# PT_2016_PB_MAIN_Rev1.net
KiCad netlist of a schematic drawn in EAGLE
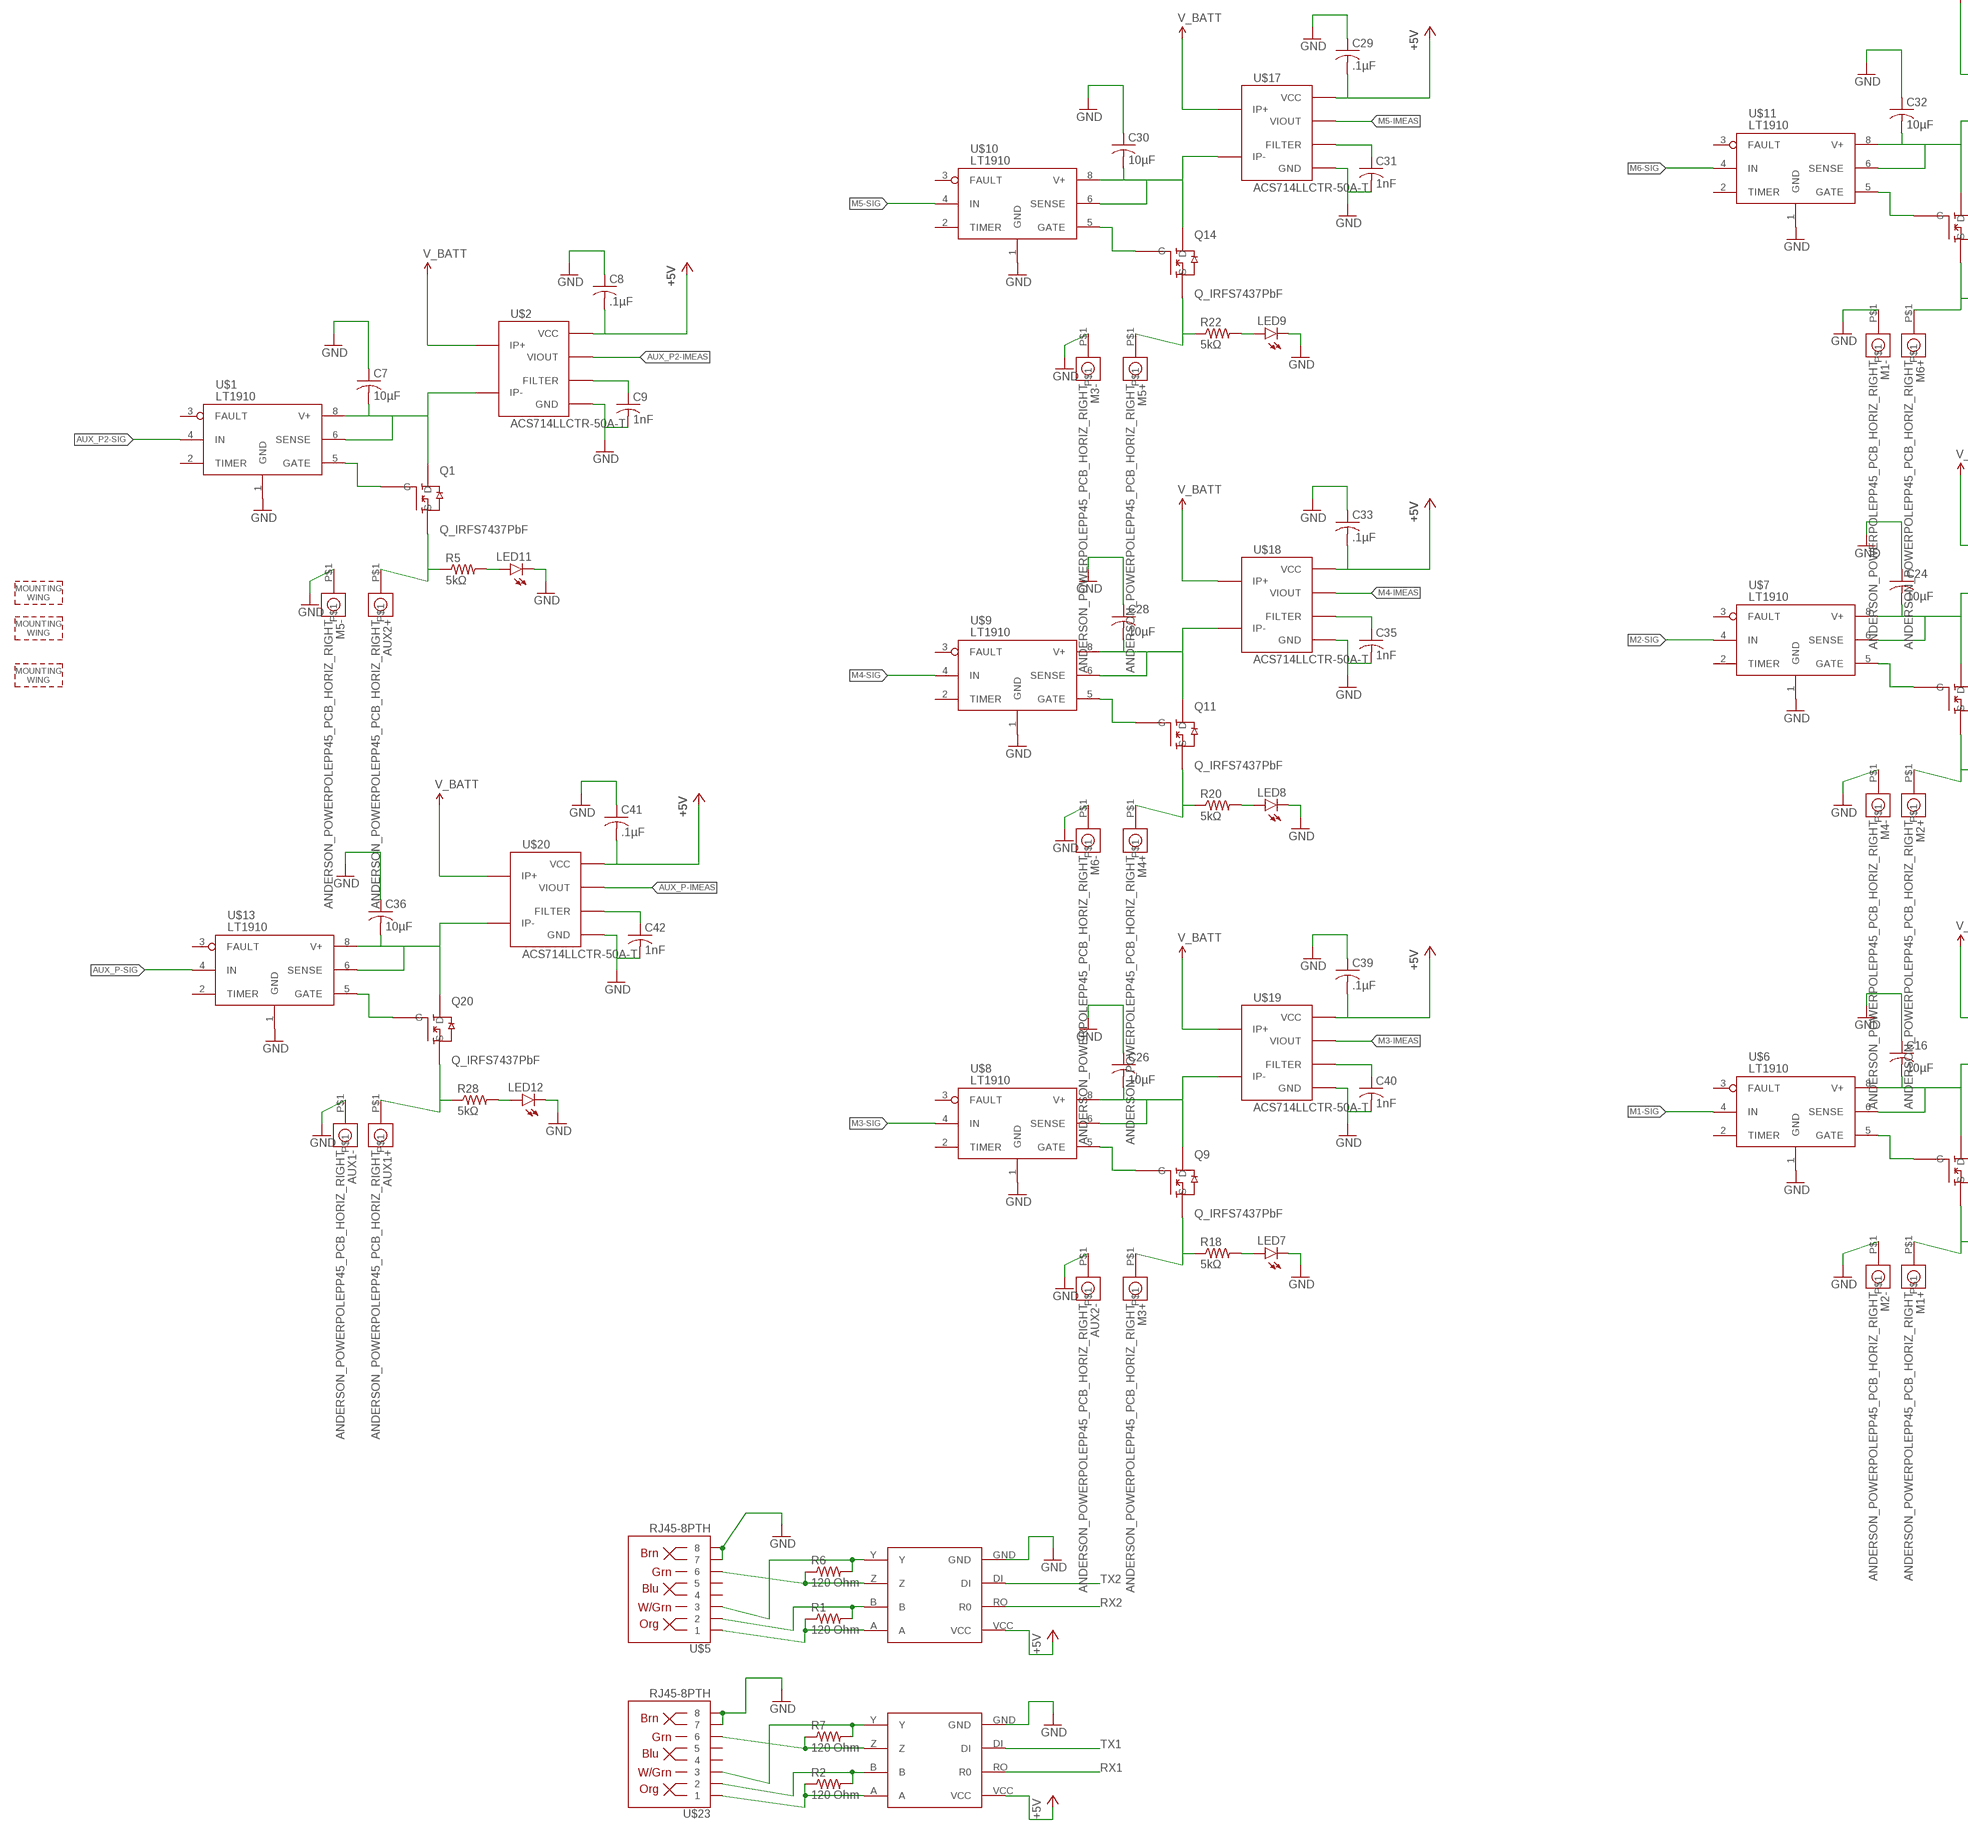
[diagram p0: schematic, sheet 1, part 1 of 3]
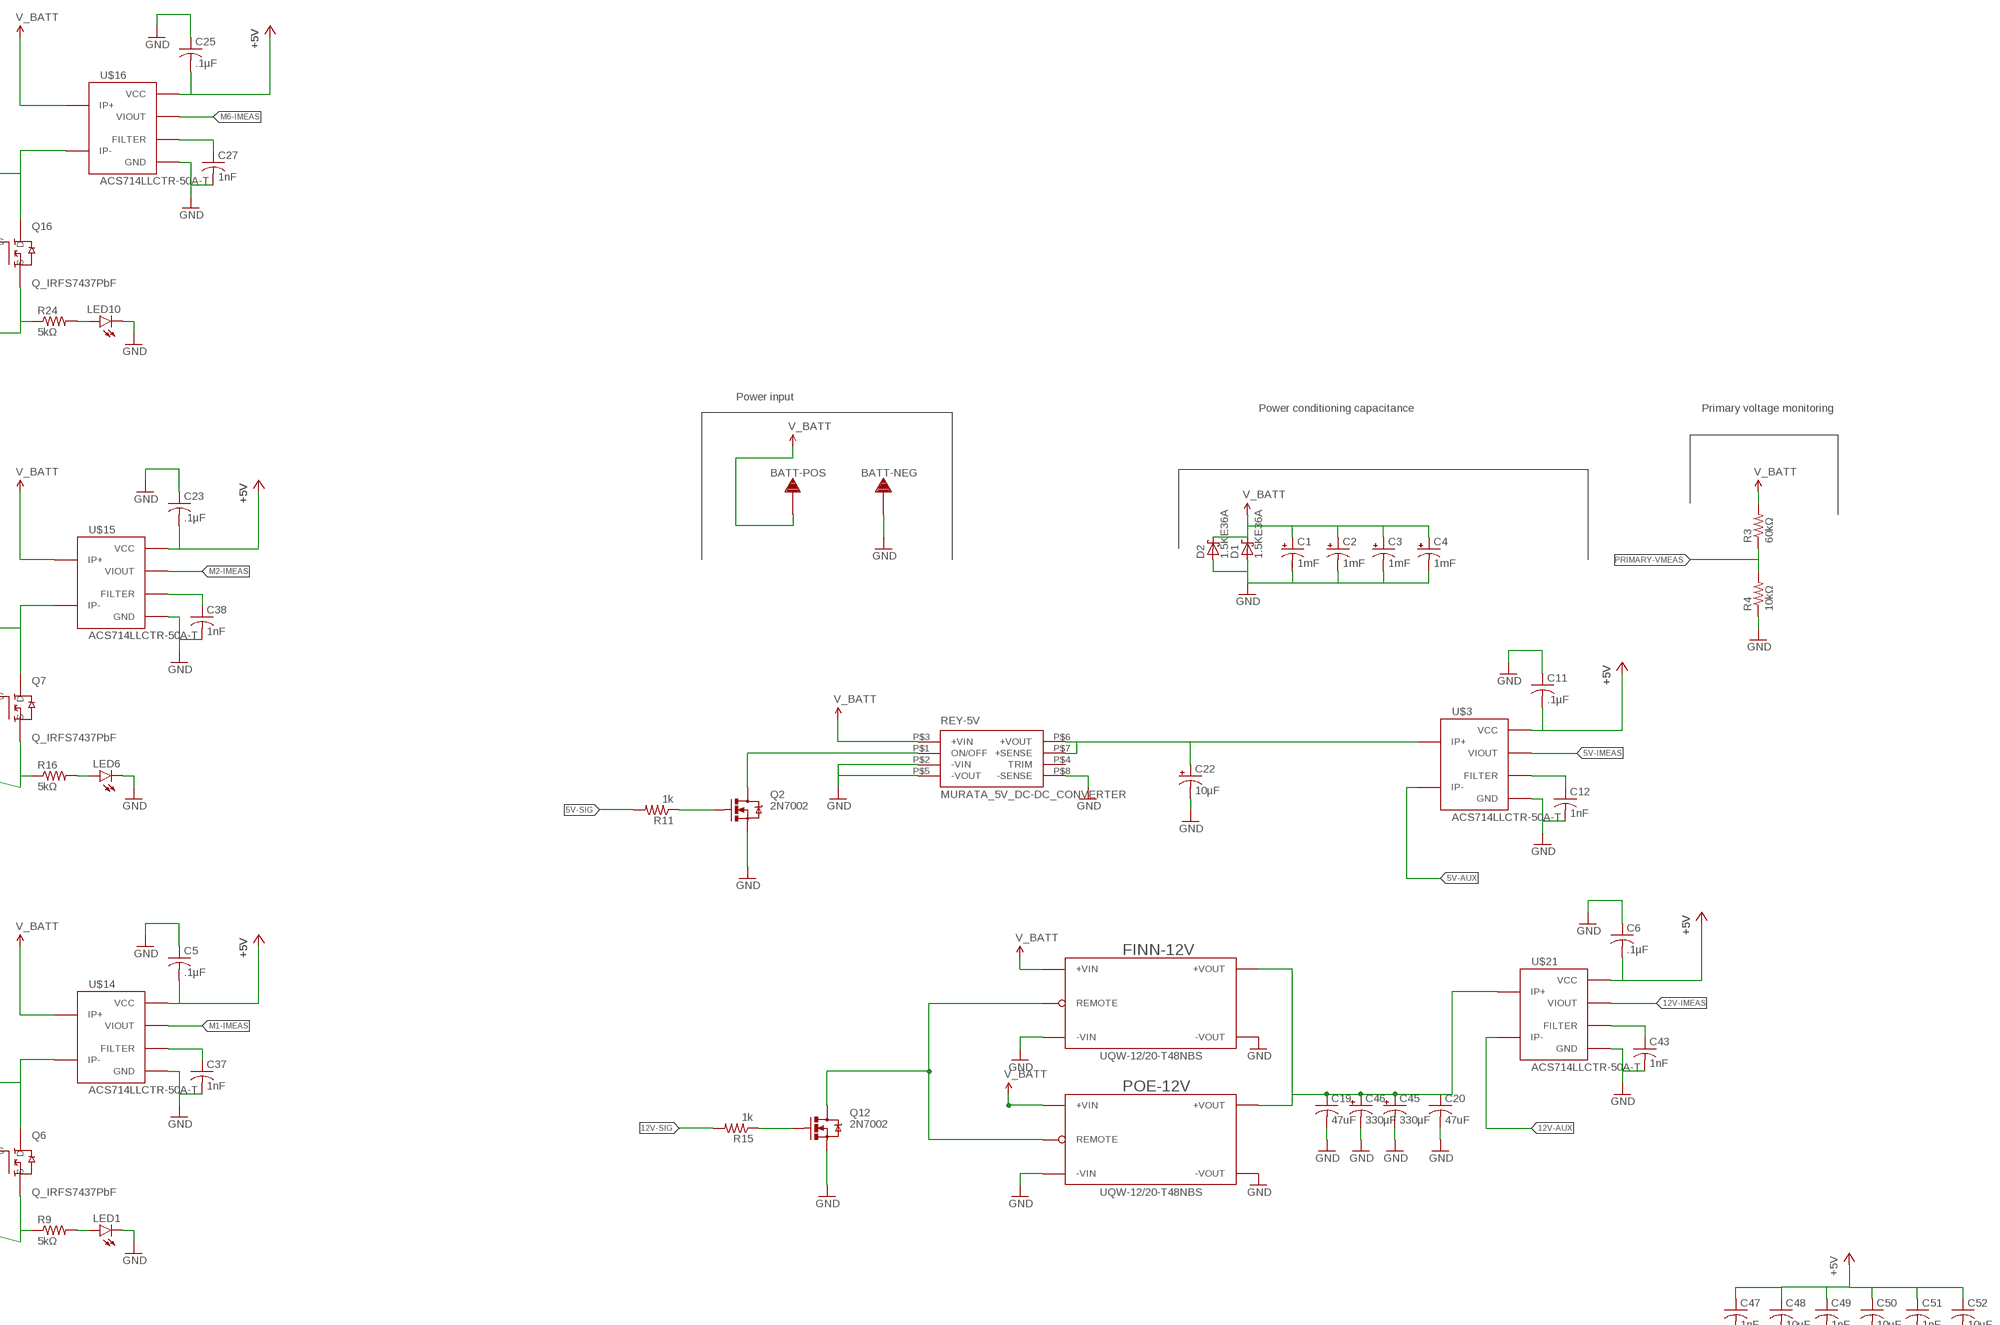
[diagram p1: schematic, sheet 1, part 2 of 3]
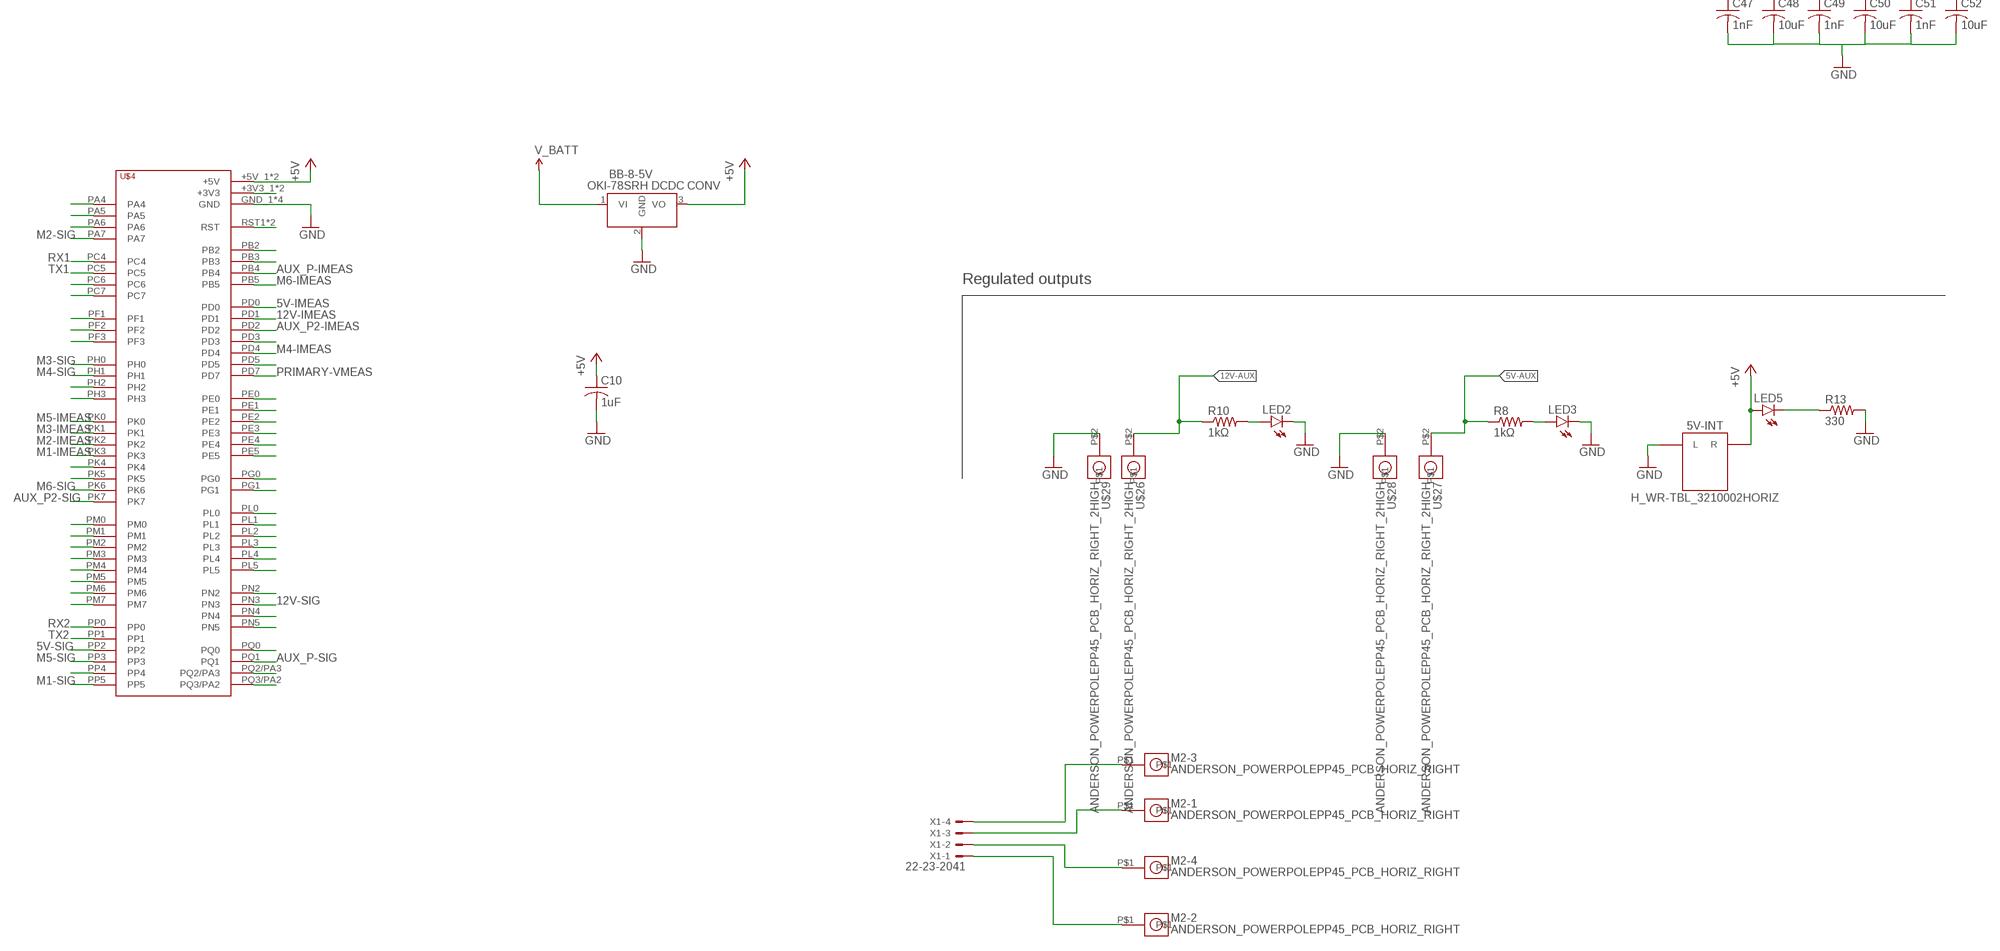
[diagram p2: schematic, sheet 1, part 3 of 3]

(export (version "E")
  (design (tool "Eeschema 10.0.6"))
  (components
    (comp (ref "5V-INT")
      (value "H_WR-TBL_3210002HORIZ")
      (footprint "eagle-import:691322110002")
      (libsource (lib "eagle-import") (part "H_WR-TBL_3210002HORIZ"))
    )
    (comp (ref "AUX1+")
      (value "ANDERSON_POWERPOLEPP45_PCB_HORIZ_RIGHT")
      (footprint "eagle-import:APP45_PCB_HORIZ_RIGHT")
      (libsource (lib "eagle-import") (part "ANDERSON_POWERPOLEPP45_PCB_HORIZ_RIGHT"))
    )
    (comp (ref "AUX1-")
      (value "ANDERSON_POWERPOLEPP45_PCB_HORIZ_RIGHT")
      (footprint "eagle-import:APP45_PCB_HORIZ_RIGHT")
      (libsource (lib "eagle-import") (part "ANDERSON_POWERPOLEPP45_PCB_HORIZ_RIGHT"))
    )
    (comp (ref "AUX2+")
      (value "ANDERSON_POWERPOLEPP45_PCB_HORIZ_RIGHT")
      (footprint "eagle-import:APP45_PCB_HORIZ_RIGHT")
      (libsource (lib "eagle-import") (part "ANDERSON_POWERPOLEPP45_PCB_HORIZ_RIGHT"))
    )
    (comp (ref "AUX2-")
      (value "ANDERSON_POWERPOLEPP45_PCB_HORIZ_RIGHT")
      (footprint "eagle-import:APP45_PCB_HORIZ_RIGHT")
      (libsource (lib "eagle-import") (part "ANDERSON_POWERPOLEPP45_PCB_HORIZ_RIGHT"))
    )
    (comp (ref "BATT-NEG")
      (value "TERMINAL_HOLE")
      (footprint "eagle-import:LARGE_TERMINAL_HOLE")
      (libsource (lib "eagle-import") (part "TERMINAL_HOLE"))
    )
    (comp (ref "BATT-POS")
      (value "TERMINAL_HOLE")
      (footprint "eagle-import:LARGE_TERMINAL_HOLE")
      (libsource (lib "eagle-import") (part "TERMINAL_HOLE"))
    )
    (comp (ref "BB-8-5V")
      (value "Q_OKI-78SR")
      (footprint "eagle-import:OKI-78SRH")
      (libsource (lib "eagle-import") (part "Q_OKI-78SR"))
    )
    (comp (ref "C1")
      (value "1mF")
      (footprint "eagle-import:C_12.5MM")
      (libsource (lib "eagle-import") (part "C_POL12.5MM_NORMAL"))
    )
    (comp (ref "C2")
      (value "1mF")
      (footprint "eagle-import:C_12.5MM")
      (libsource (lib "eagle-import") (part "C_POL12.5MM_NORMAL"))
    )
    (comp (ref "C3")
      (value "1mF")
      (footprint "eagle-import:C_12.5MM")
      (libsource (lib "eagle-import") (part "C_POL12.5MM_NORMAL"))
    )
    (comp (ref "C4")
      (value "1mF")
      (footprint "eagle-import:C_12.5MM")
      (libsource (lib "eagle-import") (part "C_POL12.5MM_NORMAL"))
    )
    (comp (ref "C5")
      (value ".1µF")
      (footprint "eagle-import:C1206")
      (libsource (lib "eagle-import") (part "C-USC1206"))
    )
    (comp (ref "C6")
      (value ".1µF")
      (footprint "eagle-import:C1206")
      (libsource (lib "eagle-import") (part "C-USC1206"))
    )
    (comp (ref "C7")
      (value "10µF")
      (footprint "eagle-import:C1206")
      (libsource (lib "eagle-import") (part "C-USC1206"))
    )
    (comp (ref "C8")
      (value ".1µF")
      (footprint "eagle-import:C1206")
      (libsource (lib "eagle-import") (part "C-USC1206"))
    )
    (comp (ref "C9")
      (value "1nF")
      (footprint "eagle-import:C1206")
      (libsource (lib "eagle-import") (part "C-USC1206"))
    )
    (comp (ref "C10")
      (value "1uF")
      (footprint "eagle-import:C1206")
      (libsource (lib "eagle-import") (part "C-USC1206"))
    )
    (comp (ref "C11")
      (value ".1µF")
      (footprint "eagle-import:C1206")
      (libsource (lib "eagle-import") (part "C-USC1206"))
    )
    (comp (ref "C12")
      (value "1nF")
      (footprint "eagle-import:C1206")
      (libsource (lib "eagle-import") (part "C-USC1206"))
    )
    (comp (ref "C16")
      (value "10µF")
      (footprint "eagle-import:C1206")
      (libsource (lib "eagle-import") (part "C-USC1206"))
    )
    (comp (ref "C19")
      (value "47uF")
      (footprint "eagle-import:C1206")
      (libsource (lib "eagle-import") (part "C-USC1206"))
    )
    (comp (ref "C20")
      (value "47uF")
      (footprint "eagle-import:C1206")
      (libsource (lib "eagle-import") (part "C-USC1206"))
    )
    (comp (ref "C22")
      (value "10µF")
      (footprint "eagle-import:E5-8,5")
      (libsource (lib "eagle-import") (part "CPOL-USE5-8.5"))
    )
    (comp (ref "C23")
      (value ".1µF")
      (footprint "eagle-import:C1206")
      (libsource (lib "eagle-import") (part "C-USC1206"))
    )
    (comp (ref "C24")
      (value "10µF")
      (footprint "eagle-import:C1206")
      (libsource (lib "eagle-import") (part "C-USC1206"))
    )
    (comp (ref "C25")
      (value ".1µF")
      (footprint "eagle-import:C1206")
      (libsource (lib "eagle-import") (part "C-USC1206"))
    )
    (comp (ref "C26")
      (value "10µF")
      (footprint "eagle-import:C1206")
      (libsource (lib "eagle-import") (part "C-USC1206"))
    )
    (comp (ref "C27")
      (value "1nF")
      (footprint "eagle-import:C1206")
      (libsource (lib "eagle-import") (part "C-USC1206"))
    )
    (comp (ref "C28")
      (value "10µF")
      (footprint "eagle-import:C1206")
      (libsource (lib "eagle-import") (part "C-USC1206"))
    )
    (comp (ref "C29")
      (value ".1µF")
      (footprint "eagle-import:C1206")
      (libsource (lib "eagle-import") (part "C-USC1206"))
    )
    (comp (ref "C30")
      (value "10µF")
      (footprint "eagle-import:C1206")
      (libsource (lib "eagle-import") (part "C-USC1206"))
    )
    (comp (ref "C31")
      (value "1nF")
      (footprint "eagle-import:C1206")
      (libsource (lib "eagle-import") (part "C-USC1206"))
    )
    (comp (ref "C32")
      (value "10µF")
      (footprint "eagle-import:C1206")
      (libsource (lib "eagle-import") (part "C-USC1206"))
    )
    (comp (ref "C33")
      (value ".1µF")
      (footprint "eagle-import:C1206")
      (libsource (lib "eagle-import") (part "C-USC1206"))
    )
    (comp (ref "C35")
      (value "1nF")
      (footprint "eagle-import:C1206")
      (libsource (lib "eagle-import") (part "C-USC1206"))
    )
    (comp (ref "C36")
      (value "10µF")
      (footprint "eagle-import:C1206")
      (libsource (lib "eagle-import") (part "C-USC1206"))
    )
    (comp (ref "C37")
      (value "1nF")
      (footprint "eagle-import:C1206")
      (libsource (lib "eagle-import") (part "C-USC1206"))
    )
    (comp (ref "C38")
      (value "1nF")
      (footprint "eagle-import:C1206")
      (libsource (lib "eagle-import") (part "C-USC1206"))
    )
    (comp (ref "C39")
      (value ".1µF")
      (footprint "eagle-import:C1206")
      (libsource (lib "eagle-import") (part "C-USC1206"))
    )
    (comp (ref "C40")
      (value "1nF")
      (footprint "eagle-import:C1206")
      (libsource (lib "eagle-import") (part "C-USC1206"))
    )
    (comp (ref "C41")
      (value ".1µF")
      (footprint "eagle-import:C1206")
      (libsource (lib "eagle-import") (part "C-USC1206"))
    )
    (comp (ref "C42")
      (value "1nF")
      (footprint "eagle-import:C1206")
      (libsource (lib "eagle-import") (part "C-USC1206"))
    )
    (comp (ref "C43")
      (value "1nF")
      (footprint "eagle-import:C1206")
      (libsource (lib "eagle-import") (part "C-USC1206"))
    )
    (comp (ref "C45")
      (value "330µF")
      (footprint "eagle-import:E5-8,5")
      (libsource (lib "eagle-import") (part "CPOL-USE5-8.5"))
    )
    (comp (ref "C46")
      (value "330µF")
      (footprint "eagle-import:E5-8,5")
      (libsource (lib "eagle-import") (part "CPOL-USE5-8.5"))
    )
    (comp (ref "C47")
      (value "1nF")
      (footprint "eagle-import:C1206")
      (libsource (lib "eagle-import") (part "C-USC1206"))
    )
    (comp (ref "C48")
      (value "10uF")
      (footprint "eagle-import:C1206")
      (libsource (lib "eagle-import") (part "C-USC1206"))
    )
    (comp (ref "C49")
      (value "1nF")
      (footprint "eagle-import:C1206")
      (libsource (lib "eagle-import") (part "C-USC1206"))
    )
    (comp (ref "C50")
      (value "10uF")
      (footprint "eagle-import:C1206")
      (libsource (lib "eagle-import") (part "C-USC1206"))
    )
    (comp (ref "C51")
      (value "1nF")
      (footprint "eagle-import:C1206")
      (libsource (lib "eagle-import") (part "C-USC1206"))
    )
    (comp (ref "C52")
      (value "10uF")
      (footprint "eagle-import:C1206")
      (libsource (lib "eagle-import") (part "C-USC1206"))
    )
    (comp (ref "D1")
      (value "1.5KE36A")
      (footprint "eagle-import:CB429-17")
      (libsource (lib "eagle-import") (part "15KEXX"))
    )
    (comp (ref "D2")
      (value "1.5KE36A")
      (footprint "eagle-import:CB429-17")
      (libsource (lib "eagle-import") (part "15KEXX"))
    )
    (comp (ref "FINN-12V")
      (value "UQW-12/20-T48NBS")
      (footprint "eagle-import:U-T48-QB-NO_TRIM")
      (libsource (lib "eagle-import") (part "UQW-12/20-T48NBS"))
    )
    (comp (ref "LED1")
      (value "LED1206")
      (footprint "eagle-import:LED-1206")
      (libsource (lib "eagle-import") (part "LED1206"))
    )
    (comp (ref "LED2")
      (value "LED1206")
      (footprint "eagle-import:LED-1206")
      (libsource (lib "eagle-import") (part "LED1206"))
    )
    (comp (ref "LED3")
      (value "LED1206")
      (footprint "eagle-import:LED-1206")
      (libsource (lib "eagle-import") (part "LED1206"))
    )
    (comp (ref "LED5")
      (value "LED1206")
      (footprint "eagle-import:LED-1206")
      (libsource (lib "eagle-import") (part "LED1206"))
    )
    (comp (ref "LED6")
      (value "LED1206")
      (footprint "eagle-import:LED-1206")
      (libsource (lib "eagle-import") (part "LED1206"))
    )
    (comp (ref "LED7")
      (value "LED1206")
      (footprint "eagle-import:LED-1206")
      (libsource (lib "eagle-import") (part "LED1206"))
    )
    (comp (ref "LED8")
      (value "LED1206")
      (footprint "eagle-import:LED-1206")
      (libsource (lib "eagle-import") (part "LED1206"))
    )
    (comp (ref "LED9")
      (value "LED1206")
      (footprint "eagle-import:LED-1206")
      (libsource (lib "eagle-import") (part "LED1206"))
    )
    (comp (ref "LED10")
      (value "LED1206")
      (footprint "eagle-import:LED-1206")
      (libsource (lib "eagle-import") (part "LED1206"))
    )
    (comp (ref "LED11")
      (value "LED1206")
      (footprint "eagle-import:LED-1206")
      (libsource (lib "eagle-import") (part "LED1206"))
    )
    (comp (ref "LED12")
      (value "LED1206")
      (footprint "eagle-import:LED-1206")
      (libsource (lib "eagle-import") (part "LED1206"))
    )
    (comp (ref "M1+")
      (value "ANDERSON_POWERPOLEPP45_PCB_HORIZ_RIGHT")
      (footprint "eagle-import:APP45_PCB_HORIZ_RIGHT")
      (libsource (lib "eagle-import") (part "ANDERSON_POWERPOLEPP45_PCB_HORIZ_RIGHT"))
    )
    (comp (ref "M1-")
      (value "ANDERSON_POWERPOLEPP45_PCB_HORIZ_RIGHT")
      (footprint "eagle-import:APP45_PCB_HORIZ_RIGHT")
      (libsource (lib "eagle-import") (part "ANDERSON_POWERPOLEPP45_PCB_HORIZ_RIGHT"))
    )
    (comp (ref "M2+")
      (value "ANDERSON_POWERPOLEPP45_PCB_HORIZ_RIGHT")
      (footprint "eagle-import:APP45_PCB_HORIZ_RIGHT")
      (libsource (lib "eagle-import") (part "ANDERSON_POWERPOLEPP45_PCB_HORIZ_RIGHT"))
    )
    (comp (ref "M2-")
      (value "ANDERSON_POWERPOLEPP45_PCB_HORIZ_RIGHT")
      (footprint "eagle-import:APP45_PCB_HORIZ_RIGHT")
      (libsource (lib "eagle-import") (part "ANDERSON_POWERPOLEPP45_PCB_HORIZ_RIGHT"))
    )
    (comp (ref "M2-1")
      (value "ANDERSON_POWERPOLEPP45_PCB_HORIZ_RIGHT")
      (footprint "eagle-import:APP45_PCB_HORIZ_RIGHT")
      (libsource (lib "eagle-import") (part "ANDERSON_POWERPOLEPP45_PCB_HORIZ_RIGHT"))
    )
    (comp (ref "M2-2")
      (value "ANDERSON_POWERPOLEPP45_PCB_HORIZ_RIGHT")
      (footprint "eagle-import:APP45_PCB_HORIZ_RIGHT")
      (libsource (lib "eagle-import") (part "ANDERSON_POWERPOLEPP45_PCB_HORIZ_RIGHT"))
    )
    (comp (ref "M2-3")
      (value "ANDERSON_POWERPOLEPP45_PCB_HORIZ_RIGHT")
      (footprint "eagle-import:APP45_PCB_HORIZ_RIGHT")
      (libsource (lib "eagle-import") (part "ANDERSON_POWERPOLEPP45_PCB_HORIZ_RIGHT"))
    )
    (comp (ref "M2-4")
      (value "ANDERSON_POWERPOLEPP45_PCB_HORIZ_RIGHT")
      (footprint "eagle-import:APP45_PCB_HORIZ_RIGHT")
      (libsource (lib "eagle-import") (part "ANDERSON_POWERPOLEPP45_PCB_HORIZ_RIGHT"))
    )
    (comp (ref "M3+")
      (value "ANDERSON_POWERPOLEPP45_PCB_HORIZ_RIGHT")
      (footprint "eagle-import:APP45_PCB_HORIZ_RIGHT")
      (libsource (lib "eagle-import") (part "ANDERSON_POWERPOLEPP45_PCB_HORIZ_RIGHT"))
    )
    (comp (ref "M3-")
      (value "ANDERSON_POWERPOLEPP45_PCB_HORIZ_RIGHT")
      (footprint "eagle-import:APP45_PCB_HORIZ_RIGHT")
      (libsource (lib "eagle-import") (part "ANDERSON_POWERPOLEPP45_PCB_HORIZ_RIGHT"))
    )
    (comp (ref "M4+")
      (value "ANDERSON_POWERPOLEPP45_PCB_HORIZ_RIGHT")
      (footprint "eagle-import:APP45_PCB_HORIZ_RIGHT")
      (libsource (lib "eagle-import") (part "ANDERSON_POWERPOLEPP45_PCB_HORIZ_RIGHT"))
    )
    (comp (ref "M4-")
      (value "ANDERSON_POWERPOLEPP45_PCB_HORIZ_RIGHT")
      (footprint "eagle-import:APP45_PCB_HORIZ_RIGHT")
      (libsource (lib "eagle-import") (part "ANDERSON_POWERPOLEPP45_PCB_HORIZ_RIGHT"))
    )
    (comp (ref "M5+")
      (value "ANDERSON_POWERPOLEPP45_PCB_HORIZ_RIGHT")
      (footprint "eagle-import:APP45_PCB_HORIZ_RIGHT")
      (libsource (lib "eagle-import") (part "ANDERSON_POWERPOLEPP45_PCB_HORIZ_RIGHT"))
    )
    (comp (ref "M5-")
      (value "ANDERSON_POWERPOLEPP45_PCB_HORIZ_RIGHT")
      (footprint "eagle-import:APP45_PCB_HORIZ_RIGHT")
      (libsource (lib "eagle-import") (part "ANDERSON_POWERPOLEPP45_PCB_HORIZ_RIGHT"))
    )
    (comp (ref "M6+")
      (value "ANDERSON_POWERPOLEPP45_PCB_HORIZ_RIGHT")
      (footprint "eagle-import:APP45_PCB_HORIZ_RIGHT")
      (libsource (lib "eagle-import") (part "ANDERSON_POWERPOLEPP45_PCB_HORIZ_RIGHT"))
    )
    (comp (ref "M6-")
      (value "ANDERSON_POWERPOLEPP45_PCB_HORIZ_RIGHT")
      (footprint "eagle-import:APP45_PCB_HORIZ_RIGHT")
      (libsource (lib "eagle-import") (part "ANDERSON_POWERPOLEPP45_PCB_HORIZ_RIGHT"))
    )
    (comp (ref "POE-12V")
      (value "UQW-12/20-T48NBS")
      (footprint "eagle-import:U-T48-QB-NO_TRIM")
      (libsource (lib "eagle-import") (part "UQW-12/20-T48NBS"))
    )
    (comp (ref "Q1")
      (value "Q_IRFS7437PbF")
      (footprint "eagle-import:D2PACK")
      (libsource (lib "eagle-import") (part "Q_IRF7437SMD"))
    )
    (comp (ref "Q2")
      (value "2N7002")
      (footprint "eagle-import:SOT323")
      (libsource (lib "eagle-import") (part "MOSFET-NCHANNEL2N7002PW"))
    )
    (comp (ref "Q6")
      (value "Q_IRFS7437PbF")
      (footprint "eagle-import:D2PACK")
      (libsource (lib "eagle-import") (part "Q_IRF7437SMD"))
    )
    (comp (ref "Q7")
      (value "Q_IRFS7437PbF")
      (footprint "eagle-import:D2PACK")
      (libsource (lib "eagle-import") (part "Q_IRF7437SMD"))
    )
    (comp (ref "Q9")
      (value "Q_IRFS7437PbF")
      (footprint "eagle-import:D2PACK")
      (libsource (lib "eagle-import") (part "Q_IRF7437SMD"))
    )
    (comp (ref "Q11")
      (value "Q_IRFS7437PbF")
      (footprint "eagle-import:D2PACK")
      (libsource (lib "eagle-import") (part "Q_IRF7437SMD"))
    )
    (comp (ref "Q12")
      (value "2N7002")
      (footprint "eagle-import:SOT323")
      (libsource (lib "eagle-import") (part "MOSFET-NCHANNEL2N7002PW"))
    )
    (comp (ref "Q14")
      (value "Q_IRFS7437PbF")
      (footprint "eagle-import:D2PACK")
      (libsource (lib "eagle-import") (part "Q_IRF7437SMD"))
    )
    (comp (ref "Q16")
      (value "Q_IRFS7437PbF")
      (footprint "eagle-import:D2PACK")
      (libsource (lib "eagle-import") (part "Q_IRF7437SMD"))
    )
    (comp (ref "Q20")
      (value "Q_IRFS7437PbF")
      (footprint "eagle-import:D2PACK")
      (libsource (lib "eagle-import") (part "Q_IRF7437SMD"))
    )
    (comp (ref "R1")
      (value "120 Ohm")
      (footprint "eagle-import:1206")
      (libsource (lib "eagle-import") (part "RESISTOR1206"))
    )
    (comp (ref "R2")
      (value "120 Ohm")
      (footprint "eagle-import:1206")
      (libsource (lib "eagle-import") (part "RESISTOR1206"))
    )
    (comp (ref "R3")
      (value "60kΩ")
      (footprint "eagle-import:R1206")
      (libsource (lib "eagle-import") (part "R-US_R1206"))
    )
    (comp (ref "R4")
      (value "10kΩ")
      (footprint "eagle-import:R1206")
      (libsource (lib "eagle-import") (part "R-US_R1206"))
    )
    (comp (ref "R5")
      (value "5kΩ")
      (footprint "eagle-import:1206")
      (libsource (lib "eagle-import") (part "RESISTOR1206"))
    )
    (comp (ref "R6")
      (value "120 Ohm")
      (footprint "eagle-import:1206")
      (libsource (lib "eagle-import") (part "RESISTOR1206"))
    )
    (comp (ref "R7")
      (value "120 Ohm")
      (footprint "eagle-import:1206")
      (libsource (lib "eagle-import") (part "RESISTOR1206"))
    )
    (comp (ref "R8")
      (value "1kΩ")
      (footprint "eagle-import:1206")
      (libsource (lib "eagle-import") (part "RESISTOR1206"))
    )
    (comp (ref "R9")
      (value "5kΩ")
      (footprint "eagle-import:1206")
      (libsource (lib "eagle-import") (part "RESISTOR1206"))
    )
    (comp (ref "R10")
      (value "1kΩ")
      (footprint "eagle-import:1206")
      (libsource (lib "eagle-import") (part "RESISTOR1206"))
    )
    (comp (ref "R11")
      (value "1k")
      (footprint "eagle-import:R1206")
      (libsource (lib "eagle-import") (part "R-US_R1206"))
    )
    (comp (ref "R13")
      (value "330")
      (footprint "eagle-import:1206")
      (libsource (lib "eagle-import") (part "RESISTOR1206"))
    )
    (comp (ref "R15")
      (value "1k")
      (footprint "eagle-import:R1206")
      (libsource (lib "eagle-import") (part "R-US_R1206"))
    )
    (comp (ref "R16")
      (value "5kΩ")
      (footprint "eagle-import:1206")
      (libsource (lib "eagle-import") (part "RESISTOR1206"))
    )
    (comp (ref "R18")
      (value "5kΩ")
      (footprint "eagle-import:1206")
      (libsource (lib "eagle-import") (part "RESISTOR1206"))
    )
    (comp (ref "R20")
      (value "5kΩ")
      (footprint "eagle-import:1206")
      (libsource (lib "eagle-import") (part "RESISTOR1206"))
    )
    (comp (ref "R22")
      (value "5kΩ")
      (footprint "eagle-import:1206")
      (libsource (lib "eagle-import") (part "RESISTOR1206"))
    )
    (comp (ref "R24")
      (value "5kΩ")
      (footprint "eagle-import:1206")
      (libsource (lib "eagle-import") (part "RESISTOR1206"))
    )
    (comp (ref "R28")
      (value "5kΩ")
      (footprint "eagle-import:1206")
      (libsource (lib "eagle-import") (part "RESISTOR1206"))
    )
    (comp (ref "REY-5V")
      (value "MURATA_5V_DC-DC_CONVERTER")
      (footprint "eagle-import:MURATA_5V_DC-DC_CONVERTER")
      (libsource (lib "eagle-import") (part "MURATA_5V_DC-DC_CONVERTER"))
    )
    (comp (ref "U$1")
      (value "LT1910")
      (footprint "eagle-import:SO8")
      (libsource (lib "eagle-import") (part "LT1910"))
    )
    (comp (ref "U$2")
      (value "ACS714LLCTR-50A-T")
      (footprint "eagle-import:SOIC8_ACS711_SKETCH")
      (libsource (lib "eagle-import") (part "Q_ACS714_SKETCH"))
    )
    (comp (ref "U$3")
      (value "ACS714LLCTR-50A-T")
      (footprint "eagle-import:SOIC8_ACS711")
      (libsource (lib "eagle-import") (part "Q_ACS714"))
    )
    (comp (ref "U$4")
      (value "TIVA-C-CONNECTED")
      (footprint "eagle-import:TIVA-C-CONNECTED")
      (libsource (lib "eagle-import") (part "TIVA-C-CONNECTED"))
    )
    (comp (ref "U$5")
      (value "RJ45-8PTH")
      (footprint "eagle-import:RJ45-8")
      (libsource (lib "eagle-import") (part "RJ45-8PTH"))
    )
    (comp (ref "U$6")
      (value "LT1910")
      (footprint "eagle-import:SO8")
      (libsource (lib "eagle-import") (part "LT1910"))
    )
    (comp (ref "U$7")
      (value "LT1910")
      (footprint "eagle-import:SO8")
      (libsource (lib "eagle-import") (part "LT1910"))
    )
    (comp (ref "U$8")
      (value "LT1910")
      (footprint "eagle-import:SO8")
      (libsource (lib "eagle-import") (part "LT1910"))
    )
    (comp (ref "U$9")
      (value "LT1910")
      (footprint "eagle-import:SO8")
      (libsource (lib "eagle-import") (part "LT1910"))
    )
    (comp (ref "U$10")
      (value "LT1910")
      (footprint "eagle-import:SO8")
      (libsource (lib "eagle-import") (part "LT1910"))
    )
    (comp (ref "U$11")
      (value "LT1910")
      (footprint "eagle-import:SO8")
      (libsource (lib "eagle-import") (part "LT1910"))
    )
    (comp (ref "U$12")
      (value "MAX3077")
      (footprint "eagle-import:MAX3070E")
      (libsource (lib "eagle-import") (part "MAX3077"))
    )
    (comp (ref "U$13")
      (value "LT1910")
      (footprint "eagle-import:SO8")
      (libsource (lib "eagle-import") (part "LT1910"))
    )
    (comp (ref "U$14")
      (value "ACS714LLCTR-50A-T")
      (footprint "eagle-import:SOIC8_ACS711_SKETCH")
      (libsource (lib "eagle-import") (part "Q_ACS714_SKETCH"))
    )
    (comp (ref "U$15")
      (value "ACS714LLCTR-50A-T")
      (footprint "eagle-import:SOIC8_ACS711_SKETCH")
      (libsource (lib "eagle-import") (part "Q_ACS714_SKETCH"))
    )
    (comp (ref "U$16")
      (value "ACS714LLCTR-50A-T")
      (footprint "eagle-import:SOIC8_ACS711_SKETCH")
      (libsource (lib "eagle-import") (part "Q_ACS714_SKETCH"))
    )
    (comp (ref "U$17")
      (value "ACS714LLCTR-50A-T")
      (footprint "eagle-import:SOIC8_ACS711_SKETCH")
      (libsource (lib "eagle-import") (part "Q_ACS714_SKETCH"))
    )
    (comp (ref "U$18")
      (value "ACS714LLCTR-50A-T")
      (footprint "eagle-import:SOIC8_ACS711_SKETCH")
      (libsource (lib "eagle-import") (part "Q_ACS714_SKETCH"))
    )
    (comp (ref "U$19")
      (value "ACS714LLCTR-50A-T")
      (footprint "eagle-import:SOIC8_ACS711_SKETCH")
      (libsource (lib "eagle-import") (part "Q_ACS714_SKETCH"))
    )
    (comp (ref "U$20")
      (value "ACS714LLCTR-50A-T")
      (footprint "eagle-import:SOIC8_ACS711_SKETCH")
      (libsource (lib "eagle-import") (part "Q_ACS714_SKETCH"))
    )
    (comp (ref "U$21")
      (value "ACS714LLCTR-50A-T")
      (footprint "eagle-import:SOIC8_ACS711")
      (libsource (lib "eagle-import") (part "Q_ACS714"))
    )
    (comp (ref "U$23")
      (value "RJ45-8PTH")
      (footprint "eagle-import:RJ45-8")
      (libsource (lib "eagle-import") (part "RJ45-8PTH"))
    )
    (comp (ref "U$24")
      (value "MAX3077")
      (footprint "eagle-import:MAX3070E")
      (libsource (lib "eagle-import") (part "MAX3077"))
    )
    (comp (ref "U$25")
      (value "APP_MOUTING_WINGHORIZ")
      (footprint "eagle-import:APP45_MOUNTING_WING_HORIZ")
      (libsource (lib "eagle-import") (part "APP_MOUTING_WINGHORIZ"))
    )
    (comp (ref "U$26")
      (value "ANDERSON_POWERPOLEPP45_PCB_HORIZ_RIGHT_2HIGH")
      (footprint "eagle-import:APP45_PCB_HORIZ_RIGHT_2HIGH")
      (libsource (lib "eagle-import") (part "ANDERSON_POWERPOLEPP45_PCB_HORIZ_RIGHT_2HIGH"))
    )
    (comp (ref "U$27")
      (value "ANDERSON_POWERPOLEPP45_PCB_HORIZ_RIGHT_2HIGH")
      (footprint "eagle-import:APP45_PCB_HORIZ_RIGHT_2HIGH")
      (libsource (lib "eagle-import") (part "ANDERSON_POWERPOLEPP45_PCB_HORIZ_RIGHT_2HIGH"))
    )
    (comp (ref "U$28")
      (value "ANDERSON_POWERPOLEPP45_PCB_HORIZ_RIGHT_2HIGH")
      (footprint "eagle-import:APP45_PCB_HORIZ_RIGHT_2HIGH")
      (libsource (lib "eagle-import") (part "ANDERSON_POWERPOLEPP45_PCB_HORIZ_RIGHT_2HIGH"))
    )
    (comp (ref "U$29")
      (value "ANDERSON_POWERPOLEPP45_PCB_HORIZ_RIGHT_2HIGH")
      (footprint "eagle-import:APP45_PCB_HORIZ_RIGHT_2HIGH")
      (libsource (lib "eagle-import") (part "ANDERSON_POWERPOLEPP45_PCB_HORIZ_RIGHT_2HIGH"))
    )
    (comp (ref "U$41")
      (value "APP_MOUTING_WINGHORIZ")
      (footprint "eagle-import:APP45_MOUNTING_WING_HORIZ")
      (libsource (lib "eagle-import") (part "APP_MOUTING_WINGHORIZ"))
    )
    (comp (ref "U$42")
      (value "APP_MOUTING_WINGHORIZ")
      (footprint "eagle-import:APP45_MOUNTING_WING_HORIZ")
      (libsource (lib "eagle-import") (part "APP_MOUTING_WINGHORIZ"))
    )
    (comp (ref "X1")
      (value "22-23-2041")
      (footprint "eagle-import:22-23-2041")
      (fields (field (name "MF") "MOLEX"))
      (libsource (lib "eagle-import") (part "22-23-2041"))
    )
  )
  (nets
    (net (code "1") (name "+5V") (class "Default")
      (node (ref "5V-INT") (pin "R") (pinfunction "R_R") (pintype "bidirectional"))
      (node (ref "BB-8-5V") (pin "3") (pinfunction "VO_3") (pintype "bidirectional"))
      (node (ref "C10") (pin "1") (pinfunction "1_1") (pintype "passive"))
      (node (ref "C11") (pin "2") (pinfunction "2_2") (pintype "passive"))
      (node (ref "C23") (pin "2") (pinfunction "2_2") (pintype "passive"))
      (node (ref "C25") (pin "2") (pinfunction "2_2") (pintype "passive"))
      (node (ref "C29") (pin "2") (pinfunction "2_2") (pintype "passive"))
      (node (ref "C33") (pin "2") (pinfunction "2_2") (pintype "passive"))
      (node (ref "C39") (pin "2") (pinfunction "2_2") (pintype "passive"))
      (node (ref "C41") (pin "2") (pinfunction "2_2") (pintype "passive"))
      (node (ref "C47") (pin "1") (pinfunction "1_1") (pintype "passive"))
      (node (ref "C48") (pin "1") (pinfunction "1_1") (pintype "passive"))
      (node (ref "C49") (pin "1") (pinfunction "1_1") (pintype "passive"))
      (node (ref "C5") (pin "2") (pinfunction "2_2") (pintype "passive"))
      (node (ref "C50") (pin "1") (pinfunction "1_1") (pintype "passive"))
      (node (ref "C51") (pin "1") (pinfunction "1_1") (pintype "passive"))
      (node (ref "C52") (pin "1") (pinfunction "1_1") (pintype "passive"))
      (node (ref "C6") (pin "2") (pinfunction "2_2") (pintype "passive"))
      (node (ref "C8") (pin "2") (pinfunction "2_2") (pintype "passive"))
      (node (ref "LED5") (pin "A") (pinfunction "A_A") (pintype "passive"))
      (node (ref "U$12") (pin "VCC") (pinfunction "VCC_VCC") (pintype "bidirectional"))
      (node (ref "U$14") (pin "8") (pinfunction "VCC_8") (pintype "bidirectional"))
      (node (ref "U$15") (pin "8") (pinfunction "VCC_8") (pintype "bidirectional"))
      (node (ref "U$16") (pin "8") (pinfunction "VCC_8") (pintype "bidirectional"))
      (node (ref "U$17") (pin "8") (pinfunction "VCC_8") (pintype "bidirectional"))
      (node (ref "U$18") (pin "8") (pinfunction "VCC_8") (pintype "bidirectional"))
      (node (ref "U$19") (pin "8") (pinfunction "VCC_8") (pintype "bidirectional"))
      (node (ref "U$2") (pin "8") (pinfunction "VCC_8") (pintype "bidirectional"))
      (node (ref "U$20") (pin "8") (pinfunction "VCC_8") (pintype "bidirectional"))
      (node (ref "U$21") (pin "8") (pinfunction "VCC_8") (pintype "bidirectional"))
      (node (ref "U$24") (pin "VCC") (pinfunction "VCC_VCC") (pintype "bidirectional"))
      (node (ref "U$3") (pin "8") (pinfunction "VCC_8") (pintype "bidirectional"))
      (node (ref "U$4") (pin "+5V_1") (pinfunction "+5V_+5V_1") (pintype "bidirectional"))
      (node (ref "U$4") (pin "+5V_2") (pinfunction "+5V_+5V_2") (pintype "bidirectional"))
    )
    (net (code "2") (name "/RX1") (class "Default")
      (node (ref "U$24") (pin "RO") (pinfunction "R0_RO") (pintype "bidirectional"))
      (node (ref "U$4") (pin "PC4") (pinfunction "PC4_PC4") (pintype "bidirectional"))
    )
    (net (code "3") (name "/RX2") (class "Default")
      (node (ref "U$12") (pin "RO") (pinfunction "R0_RO") (pintype "bidirectional"))
      (node (ref "U$4") (pin "PP0") (pinfunction "PP0_PP0") (pintype "bidirectional"))
    )
    (net (code "4") (name "/TX1") (class "Default")
      (node (ref "U$24") (pin "DI") (pinfunction "DI_DI") (pintype "bidirectional"))
      (node (ref "U$4") (pin "PC5") (pinfunction "PC5_PC5") (pintype "bidirectional"))
    )
    (net (code "5") (name "/TX2") (class "Default")
      (node (ref "U$12") (pin "DI") (pinfunction "DI_DI") (pintype "bidirectional"))
      (node (ref "U$4") (pin "PP1") (pinfunction "PP1_PP1") (pintype "bidirectional"))
    )
    (net (code "6") (name "5V-AUX") (class "Default")
      (node (ref "R8") (pin "1") (pinfunction "1_1") (pintype "passive"))
      (node (ref "U$27") (pin "P$2") (pinfunction "P$1_P$2") (pintype "bidirectional"))
      (node (ref "U$3") (pin "4") (pinfunction "IP-_4") (pintype "bidirectional"))
    )
    (net (code "7") (name "5V-IMEAS") (class "Default")
      (node (ref "U$3") (pin "7") (pinfunction "VIOUT_7") (pintype "bidirectional"))
      (node (ref "U$4") (pin "PD0") (pinfunction "PD0_PD0") (pintype "bidirectional"))
    )
    (net (code "8") (name "5V-SIG") (class "Default")
      (node (ref "R11") (pin "2") (pinfunction "2_2") (pintype "passive"))
      (node (ref "U$4") (pin "PP2") (pinfunction "PP2_PP2") (pintype "bidirectional"))
    )
    (net (code "9") (name "12V-AUX") (class "Default")
      (node (ref "R10") (pin "1") (pinfunction "1_1") (pintype "passive"))
      (node (ref "U$21") (pin "4") (pinfunction "IP-_4") (pintype "bidirectional"))
      (node (ref "U$26") (pin "P$2") (pinfunction "P$1_P$2") (pintype "bidirectional"))
    )
    (net (code "10") (name "12V-IMEAS") (class "Default")
      (node (ref "U$21") (pin "7") (pinfunction "VIOUT_7") (pintype "bidirectional"))
      (node (ref "U$4") (pin "PD1") (pinfunction "PD1_PD1") (pintype "bidirectional"))
    )
    (net (code "11") (name "12V-SIG") (class "Default")
      (node (ref "R15") (pin "2") (pinfunction "2_2") (pintype "passive"))
      (node (ref "U$4") (pin "PN3") (pinfunction "PN3_PN3") (pintype "bidirectional"))
    )
    (net (code "12") (name "AUX_P-IMEAS") (class "Default")
      (node (ref "U$20") (pin "7") (pinfunction "VIOUT_7") (pintype "bidirectional"))
      (node (ref "U$4") (pin "PB4") (pinfunction "PB4_PB4") (pintype "bidirectional"))
    )
    (net (code "13") (name "AUX_P-SIG") (class "Default")
      (node (ref "U$13") (pin "4") (pinfunction "IN_4") (pintype "bidirectional"))
      (node (ref "U$4") (pin "PQ1") (pinfunction "PQ1_PQ1") (pintype "bidirectional"))
    )
    (net (code "14") (name "AUX_P2-IMEAS") (class "Default")
      (node (ref "U$2") (pin "7") (pinfunction "VIOUT_7") (pintype "bidirectional"))
      (node (ref "U$4") (pin "PD2") (pinfunction "PD2_PD2") (pintype "bidirectional"))
    )
    (net (code "15") (name "AUX_P2-SIG") (class "Default")
      (node (ref "U$1") (pin "4") (pinfunction "IN_4") (pintype "bidirectional"))
      (node (ref "U$4") (pin "PK7") (pinfunction "PK7_PK7") (pintype "bidirectional"))
    )
    (net (code "16") (name "GND") (class "Default")
      (node (ref "5V-INT") (pin "L") (pinfunction "L_L") (pintype "bidirectional"))
      (node (ref "AUX1-") (pin "P$1") (pinfunction "P$1_P$1") (pintype "bidirectional"))
      (node (ref "AUX2-") (pin "P$1") (pinfunction "P$1_P$1") (pintype "bidirectional"))
      (node (ref "BATT-NEG") (pin "P$1") (pinfunction "P$1_P$1") (pintype "bidirectional"))
      (node (ref "BB-8-5V") (pin "2") (pinfunction "GND_2") (pintype "bidirectional"))
      (node (ref "C1") (pin "-") (pinfunction "-_-") (pintype "passive"))
      (node (ref "C10") (pin "2") (pinfunction "2_2") (pintype "passive"))
      (node (ref "C11") (pin "1") (pinfunction "1_1") (pintype "passive"))
      (node (ref "C12") (pin "2") (pinfunction "2_2") (pintype "passive"))
      (node (ref "C16") (pin "1") (pinfunction "1_1") (pintype "passive"))
      (node (ref "C19") (pin "2") (pinfunction "2_2") (pintype "passive"))
      (node (ref "C2") (pin "-") (pinfunction "-_-") (pintype "passive"))
      (node (ref "C20") (pin "2") (pinfunction "2_2") (pintype "passive"))
      (node (ref "C22") (pin "-") (pinfunction "-_-") (pintype "passive"))
      (node (ref "C23") (pin "1") (pinfunction "1_1") (pintype "passive"))
      (node (ref "C24") (pin "1") (pinfunction "1_1") (pintype "passive"))
      (node (ref "C25") (pin "1") (pinfunction "1_1") (pintype "passive"))
      (node (ref "C26") (pin "1") (pinfunction "1_1") (pintype "passive"))
      (node (ref "C27") (pin "2") (pinfunction "2_2") (pintype "passive"))
      (node (ref "C28") (pin "1") (pinfunction "1_1") (pintype "passive"))
      (node (ref "C29") (pin "1") (pinfunction "1_1") (pintype "passive"))
      (node (ref "C3") (pin "-") (pinfunction "-_-") (pintype "passive"))
      (node (ref "C30") (pin "1") (pinfunction "1_1") (pintype "passive"))
      (node (ref "C31") (pin "2") (pinfunction "2_2") (pintype "passive"))
      (node (ref "C32") (pin "1") (pinfunction "1_1") (pintype "passive"))
      (node (ref "C33") (pin "1") (pinfunction "1_1") (pintype "passive"))
      (node (ref "C35") (pin "2") (pinfunction "2_2") (pintype "passive"))
      (node (ref "C36") (pin "1") (pinfunction "1_1") (pintype "passive"))
      (node (ref "C37") (pin "2") (pinfunction "2_2") (pintype "passive"))
      (node (ref "C38") (pin "2") (pinfunction "2_2") (pintype "passive"))
      (node (ref "C39") (pin "1") (pinfunction "1_1") (pintype "passive"))
      (node (ref "C4") (pin "-") (pinfunction "-_-") (pintype "passive"))
      (node (ref "C40") (pin "2") (pinfunction "2_2") (pintype "passive"))
      (node (ref "C41") (pin "1") (pinfunction "1_1") (pintype "passive"))
      (node (ref "C42") (pin "2") (pinfunction "2_2") (pintype "passive"))
      (node (ref "C43") (pin "2") (pinfunction "2_2") (pintype "passive"))
      (node (ref "C45") (pin "-") (pinfunction "-_-") (pintype "passive"))
      (node (ref "C46") (pin "-") (pinfunction "-_-") (pintype "passive"))
      (node (ref "C47") (pin "2") (pinfunction "2_2") (pintype "passive"))
      (node (ref "C48") (pin "2") (pinfunction "2_2") (pintype "passive"))
      (node (ref "C49") (pin "2") (pinfunction "2_2") (pintype "passive"))
      (node (ref "C5") (pin "1") (pinfunction "1_1") (pintype "passive"))
      (node (ref "C50") (pin "2") (pinfunction "2_2") (pintype "passive"))
      (node (ref "C51") (pin "2") (pinfunction "2_2") (pintype "passive"))
      (node (ref "C52") (pin "2") (pinfunction "2_2") (pintype "passive"))
      (node (ref "C6") (pin "1") (pinfunction "1_1") (pintype "passive"))
      (node (ref "C7") (pin "1") (pinfunction "1_1") (pintype "passive"))
      (node (ref "C8") (pin "1") (pinfunction "1_1") (pintype "passive"))
      (node (ref "C9") (pin "2") (pinfunction "2_2") (pintype "passive"))
      (node (ref "D1") (pin "A") (pinfunction "A_A") (pintype "passive"))
      (node (ref "D2") (pin "A") (pinfunction "A_A") (pintype "passive"))
      (node (ref "FINN-12V") (pin "3") (pinfunction "-VIN_3") (pintype "bidirectional"))
      (node (ref "FINN-12V") (pin "4") (pinfunction "-VOUT_4") (pintype "bidirectional"))
      (node (ref "LED1") (pin "C") (pinfunction "C_C") (pintype "passive"))
      (node (ref "LED10") (pin "C") (pinfunction "C_C") (pintype "passive"))
      (node (ref "LED11") (pin "C") (pinfunction "C_C") (pintype "passive"))
      (node (ref "LED12") (pin "C") (pinfunction "C_C") (pintype "passive"))
      (node (ref "LED2") (pin "C") (pinfunction "C_C") (pintype "passive"))
      (node (ref "LED3") (pin "C") (pinfunction "C_C") (pintype "passive"))
      (node (ref "LED6") (pin "C") (pinfunction "C_C") (pintype "passive"))
      (node (ref "LED7") (pin "C") (pinfunction "C_C") (pintype "passive"))
      (node (ref "LED8") (pin "C") (pinfunction "C_C") (pintype "passive"))
      (node (ref "LED9") (pin "C") (pinfunction "C_C") (pintype "passive"))
      (node (ref "M1-") (pin "P$1") (pinfunction "P$1_P$1") (pintype "bidirectional"))
      (node (ref "M2-") (pin "P$1") (pinfunction "P$1_P$1") (pintype "bidirectional"))
      (node (ref "M3-") (pin "P$1") (pinfunction "P$1_P$1") (pintype "bidirectional"))
      (node (ref "M4-") (pin "P$1") (pinfunction "P$1_P$1") (pintype "bidirectional"))
      (node (ref "M5-") (pin "P$1") (pinfunction "P$1_P$1") (pintype "bidirectional"))
      (node (ref "M6-") (pin "P$1") (pinfunction "P$1_P$1") (pintype "bidirectional"))
      (node (ref "POE-12V") (pin "3") (pinfunction "-VIN_3") (pintype "bidirectional"))
      (node (ref "POE-12V") (pin "4") (pinfunction "-VOUT_4") (pintype "bidirectional"))
      (node (ref "Q12") (pin "2") (pinfunction "S_2") (pintype "passive"))
      (node (ref "Q2") (pin "2") (pinfunction "S_2") (pintype "passive"))
      (node (ref "R13") (pin "2") (pinfunction "2_2") (pintype "passive"))
      (node (ref "R4") (pin "1") (pinfunction "1_1") (pintype "passive"))
      (node (ref "REY-5V") (pin "P$2") (pinfunction "-VIN_P$2") (pintype "bidirectional"))
      (node (ref "REY-5V") (pin "P$5") (pinfunction "-VOUT_P$5") (pintype "bidirectional"))
      (node (ref "REY-5V") (pin "P$8") (pinfunction "-SENSE_P$8") (pintype "bidirectional"))
      (node (ref "U$1") (pin "1") (pinfunction "GND_1") (pintype "bidirectional"))
      (node (ref "U$10") (pin "1") (pinfunction "GND_1") (pintype "bidirectional"))
      (node (ref "U$11") (pin "1") (pinfunction "GND_1") (pintype "bidirectional"))
      (node (ref "U$12") (pin "GND") (pinfunction "GND_GND") (pintype "bidirectional"))
      (node (ref "U$13") (pin "1") (pinfunction "GND_1") (pintype "bidirectional"))
      (node (ref "U$14") (pin "5") (pinfunction "GND_5") (pintype "bidirectional"))
      (node (ref "U$15") (pin "5") (pinfunction "GND_5") (pintype "bidirectional"))
      (node (ref "U$16") (pin "5") (pinfunction "GND_5") (pintype "bidirectional"))
      (node (ref "U$17") (pin "5") (pinfunction "GND_5") (pintype "bidirectional"))
      (node (ref "U$18") (pin "5") (pinfunction "GND_5") (pintype "bidirectional"))
      (node (ref "U$19") (pin "5") (pinfunction "GND_5") (pintype "bidirectional"))
      (node (ref "U$2") (pin "5") (pinfunction "GND_5") (pintype "bidirectional"))
      (node (ref "U$20") (pin "5") (pinfunction "GND_5") (pintype "bidirectional"))
      (node (ref "U$21") (pin "5") (pinfunction "GND_5") (pintype "bidirectional"))
      (node (ref "U$23") (pin "7") (pinfunction "7_7") (pintype "bidirectional"))
      (node (ref "U$23") (pin "8") (pinfunction "8_8") (pintype "bidirectional"))
      (node (ref "U$24") (pin "GND") (pinfunction "GND_GND") (pintype "bidirectional"))
      (node (ref "U$28") (pin "P$2") (pinfunction "P$1_P$2") (pintype "bidirectional"))
      (node (ref "U$29") (pin "P$2") (pinfunction "P$1_P$2") (pintype "bidirectional"))
      (node (ref "U$3") (pin "5") (pinfunction "GND_5") (pintype "bidirectional"))
      (node (ref "U$4") (pin "GND_1") (pinfunction "GND_GND_1") (pintype "bidirectional"))
      (node (ref "U$4") (pin "GND_2") (pinfunction "GND_GND_2") (pintype "bidirectional"))
      (node (ref "U$4") (pin "GND_3") (pinfunction "GND_GND_3") (pintype "bidirectional"))
      (node (ref "U$4") (pin "GND_4") (pinfunction "GND_GND_4") (pintype "bidirectional"))
      (node (ref "U$5") (pin "7") (pinfunction "7_7") (pintype "bidirectional"))
      (node (ref "U$5") (pin "8") (pinfunction "8_8") (pintype "bidirectional"))
      (node (ref "U$6") (pin "1") (pinfunction "GND_1") (pintype "bidirectional"))
      (node (ref "U$7") (pin "1") (pinfunction "GND_1") (pintype "bidirectional"))
      (node (ref "U$8") (pin "1") (pinfunction "GND_1") (pintype "bidirectional"))
      (node (ref "U$9") (pin "1") (pinfunction "GND_1") (pintype "bidirectional"))
    )
    (net (code "17") (name "M1-IMEAS") (class "Default")
      (node (ref "U$14") (pin "7") (pinfunction "VIOUT_7") (pintype "bidirectional"))
      (node (ref "U$4") (pin "PK3") (pinfunction "PK3_PK3") (pintype "bidirectional"))
    )
    (net (code "18") (name "M1-SIG") (class "Default")
      (node (ref "U$4") (pin "PP5") (pinfunction "PP5_PP5") (pintype "bidirectional"))
      (node (ref "U$6") (pin "4") (pinfunction "IN_4") (pintype "bidirectional"))
    )
    (net (code "19") (name "M2-IMEAS") (class "Default")
      (node (ref "U$15") (pin "7") (pinfunction "VIOUT_7") (pintype "bidirectional"))
      (node (ref "U$4") (pin "PK2") (pinfunction "PK2_PK2") (pintype "bidirectional"))
    )
    (net (code "20") (name "M2-SIG") (class "Default")
      (node (ref "U$4") (pin "PA7") (pinfunction "PA7_PA7") (pintype "bidirectional"))
      (node (ref "U$7") (pin "4") (pinfunction "IN_4") (pintype "bidirectional"))
    )
    (net (code "21") (name "M3-IMEAS") (class "Default")
      (node (ref "U$19") (pin "7") (pinfunction "VIOUT_7") (pintype "bidirectional"))
      (node (ref "U$4") (pin "PK1") (pinfunction "PK1_PK1") (pintype "bidirectional"))
    )
    (net (code "22") (name "M3-SIG") (class "Default")
      (node (ref "U$4") (pin "PH0") (pinfunction "PH0_PH0") (pintype "bidirectional"))
      (node (ref "U$8") (pin "4") (pinfunction "IN_4") (pintype "bidirectional"))
    )
    (net (code "23") (name "M4-IMEAS") (class "Default")
      (node (ref "U$18") (pin "7") (pinfunction "VIOUT_7") (pintype "bidirectional"))
      (node (ref "U$4") (pin "PD4") (pinfunction "PD4_PD4") (pintype "bidirectional"))
    )
    (net (code "24") (name "M4-SIG") (class "Default")
      (node (ref "U$4") (pin "PH1") (pinfunction "PH1_PH1") (pintype "bidirectional"))
      (node (ref "U$9") (pin "4") (pinfunction "IN_4") (pintype "bidirectional"))
    )
    (net (code "25") (name "M5-IMEAS") (class "Default")
      (node (ref "U$17") (pin "7") (pinfunction "VIOUT_7") (pintype "bidirectional"))
      (node (ref "U$4") (pin "PK0") (pinfunction "PK0_PK0") (pintype "bidirectional"))
    )
    (net (code "26") (name "M5-SIG") (class "Default")
      (node (ref "U$10") (pin "4") (pinfunction "IN_4") (pintype "bidirectional"))
      (node (ref "U$4") (pin "PP3") (pinfunction "PP3_PP3") (pintype "bidirectional"))
    )
    (net (code "27") (name "M6-IMEAS") (class "Default")
      (node (ref "U$16") (pin "7") (pinfunction "VIOUT_7") (pintype "bidirectional"))
      (node (ref "U$4") (pin "PB5") (pinfunction "PB5_PB5") (pintype "bidirectional"))
    )
    (net (code "28") (name "M6-SIG") (class "Default")
      (node (ref "U$11") (pin "4") (pinfunction "IN_4") (pintype "bidirectional"))
      (node (ref "U$4") (pin "PK6") (pinfunction "PK6_PK6") (pintype "bidirectional"))
    )
    (net (code "29") (name "Net-(FINN-12V-+VOUT)") (class "Default")
      (node (ref "C19") (pin "1") (pinfunction "1_1") (pintype "passive"))
      (node (ref "C20") (pin "1") (pinfunction "1_1") (pintype "passive"))
      (node (ref "C45") (pin "+") (pinfunction "+_+") (pintype "passive"))
      (node (ref "C46") (pin "+") (pinfunction "+_+") (pintype "passive"))
      (node (ref "FINN-12V") (pin "8") (pinfunction "+VOUT_8") (pintype "bidirectional"))
      (node (ref "POE-12V") (pin "8") (pinfunction "+VOUT_8") (pintype "bidirectional"))
      (node (ref "U$21") (pin "1") (pinfunction "IP+_1") (pintype "bidirectional"))
    )
    (net (code "30") (name "Net-(FINN-12V-REMOTE)") (class "Default")
      (node (ref "FINN-12V") (pin "2") (pinfunction "REMOTE_2") (pintype "bidirectional"))
      (node (ref "POE-12V") (pin "2") (pinfunction "REMOTE_2") (pintype "bidirectional"))
      (node (ref "Q12") (pin "3") (pinfunction "D_3") (pintype "passive"))
    )
    (net (code "31") (name "Net-(LED1-PadA)") (class "Default")
      (node (ref "LED1") (pin "A") (pinfunction "A_A") (pintype "passive"))
      (node (ref "R9") (pin "2") (pinfunction "2_2") (pintype "passive"))
    )
    (net (code "32") (name "Net-(LED2-PadA)") (class "Default")
      (node (ref "LED2") (pin "A") (pinfunction "A_A") (pintype "passive"))
      (node (ref "R10") (pin "2") (pinfunction "2_2") (pintype "passive"))
    )
    (net (code "33") (name "Net-(LED3-PadA)") (class "Default")
      (node (ref "LED3") (pin "A") (pinfunction "A_A") (pintype "passive"))
      (node (ref "R8") (pin "2") (pinfunction "2_2") (pintype "passive"))
    )
    (net (code "34") (name "Net-(LED5-PadC)") (class "Default")
      (node (ref "LED5") (pin "C") (pinfunction "C_C") (pintype "passive"))
      (node (ref "R13") (pin "1") (pinfunction "1_1") (pintype "passive"))
    )
    (net (code "35") (name "Net-(LED6-PadA)") (class "Default")
      (node (ref "LED6") (pin "A") (pinfunction "A_A") (pintype "passive"))
      (node (ref "R16") (pin "2") (pinfunction "2_2") (pintype "passive"))
    )
    (net (code "36") (name "Net-(LED7-PadA)") (class "Default")
      (node (ref "LED7") (pin "A") (pinfunction "A_A") (pintype "passive"))
      (node (ref "R18") (pin "2") (pinfunction "2_2") (pintype "passive"))
    )
    (net (code "37") (name "Net-(LED8-PadA)") (class "Default")
      (node (ref "LED8") (pin "A") (pinfunction "A_A") (pintype "passive"))
      (node (ref "R20") (pin "2") (pinfunction "2_2") (pintype "passive"))
    )
    (net (code "38") (name "Net-(LED9-PadA)") (class "Default")
      (node (ref "LED9") (pin "A") (pinfunction "A_A") (pintype "passive"))
      (node (ref "R22") (pin "2") (pinfunction "2_2") (pintype "passive"))
    )
    (net (code "39") (name "Net-(LED10-PadA)") (class "Default")
      (node (ref "LED10") (pin "A") (pinfunction "A_A") (pintype "passive"))
      (node (ref "R24") (pin "2") (pinfunction "2_2") (pintype "passive"))
    )
    (net (code "40") (name "Net-(LED11-PadA)") (class "Default")
      (node (ref "LED11") (pin "A") (pinfunction "A_A") (pintype "passive"))
      (node (ref "R5") (pin "2") (pinfunction "2_2") (pintype "passive"))
    )
    (net (code "41") (name "Net-(LED12-PadA)") (class "Default")
      (node (ref "LED12") (pin "A") (pinfunction "A_A") (pintype "passive"))
      (node (ref "R28") (pin "2") (pinfunction "2_2") (pintype "passive"))
    )
    (net (code "42") (name "Net-(Q1-D)") (class "Default")
      (node (ref "C7") (pin "2") (pinfunction "2_2") (pintype "passive"))
      (node (ref "Q1") (pin "TAB") (pinfunction "D_TAB") (pintype "bidirectional"))
      (node (ref "U$1") (pin "6") (pinfunction "SENSE_6") (pintype "bidirectional"))
      (node (ref "U$1") (pin "8") (pinfunction "V+_8") (pintype "bidirectional"))
      (node (ref "U$2") (pin "4") (pinfunction "IP-_4") (pintype "bidirectional"))
    )
    (net (code "43") (name "Net-(Q1-G)") (class "Default")
      (node (ref "Q1") (pin "1") (pinfunction "G_1") (pintype "bidirectional"))
      (node (ref "U$1") (pin "5") (pinfunction "GATE_5") (pintype "bidirectional"))
    )
    (net (code "44") (name "Net-(Q1-S)") (class "Default")
      (node (ref "AUX2+") (pin "P$1") (pinfunction "P$1_P$1") (pintype "bidirectional"))
      (node (ref "Q1") (pin "2") (pinfunction "S_2") (pintype "bidirectional"))
      (node (ref "R5") (pin "1") (pinfunction "1_1") (pintype "passive"))
    )
    (net (code "45") (name "Net-(Q2-D)") (class "Default")
      (node (ref "Q2") (pin "3") (pinfunction "D_3") (pintype "passive"))
      (node (ref "REY-5V") (pin "P$1") (pinfunction "ON/OFF_P$1") (pintype "bidirectional"))
    )
    (net (code "46") (name "Net-(Q2-G)") (class "Default")
      (node (ref "Q2") (pin "1") (pinfunction "G_1") (pintype "passive"))
      (node (ref "R11") (pin "1") (pinfunction "1_1") (pintype "passive"))
    )
    (net (code "47") (name "Net-(Q6-D)") (class "Default")
      (node (ref "C16") (pin "2") (pinfunction "2_2") (pintype "passive"))
      (node (ref "Q6") (pin "TAB") (pinfunction "D_TAB") (pintype "bidirectional"))
      (node (ref "U$14") (pin "4") (pinfunction "IP-_4") (pintype "bidirectional"))
      (node (ref "U$6") (pin "6") (pinfunction "SENSE_6") (pintype "bidirectional"))
      (node (ref "U$6") (pin "8") (pinfunction "V+_8") (pintype "bidirectional"))
    )
    (net (code "48") (name "Net-(Q6-G)") (class "Default")
      (node (ref "Q6") (pin "1") (pinfunction "G_1") (pintype "bidirectional"))
      (node (ref "U$6") (pin "5") (pinfunction "GATE_5") (pintype "bidirectional"))
    )
    (net (code "49") (name "Net-(Q6-S)") (class "Default")
      (node (ref "M1+") (pin "P$1") (pinfunction "P$1_P$1") (pintype "bidirectional"))
      (node (ref "Q6") (pin "2") (pinfunction "S_2") (pintype "bidirectional"))
      (node (ref "R9") (pin "1") (pinfunction "1_1") (pintype "passive"))
    )
    (net (code "50") (name "Net-(Q7-D)") (class "Default")
      (node (ref "C24") (pin "2") (pinfunction "2_2") (pintype "passive"))
      (node (ref "Q7") (pin "TAB") (pinfunction "D_TAB") (pintype "bidirectional"))
      (node (ref "U$15") (pin "4") (pinfunction "IP-_4") (pintype "bidirectional"))
      (node (ref "U$7") (pin "6") (pinfunction "SENSE_6") (pintype "bidirectional"))
      (node (ref "U$7") (pin "8") (pinfunction "V+_8") (pintype "bidirectional"))
    )
    (net (code "51") (name "Net-(Q7-G)") (class "Default")
      (node (ref "Q7") (pin "1") (pinfunction "G_1") (pintype "bidirectional"))
      (node (ref "U$7") (pin "5") (pinfunction "GATE_5") (pintype "bidirectional"))
    )
    (net (code "52") (name "Net-(Q7-S)") (class "Default")
      (node (ref "M2+") (pin "P$1") (pinfunction "P$1_P$1") (pintype "bidirectional"))
      (node (ref "Q7") (pin "2") (pinfunction "S_2") (pintype "bidirectional"))
      (node (ref "R16") (pin "1") (pinfunction "1_1") (pintype "passive"))
    )
    (net (code "53") (name "Net-(Q9-D)") (class "Default")
      (node (ref "C26") (pin "2") (pinfunction "2_2") (pintype "passive"))
      (node (ref "Q9") (pin "TAB") (pinfunction "D_TAB") (pintype "bidirectional"))
      (node (ref "U$19") (pin "4") (pinfunction "IP-_4") (pintype "bidirectional"))
      (node (ref "U$8") (pin "6") (pinfunction "SENSE_6") (pintype "bidirectional"))
      (node (ref "U$8") (pin "8") (pinfunction "V+_8") (pintype "bidirectional"))
    )
    (net (code "54") (name "Net-(Q9-G)") (class "Default")
      (node (ref "Q9") (pin "1") (pinfunction "G_1") (pintype "bidirectional"))
      (node (ref "U$8") (pin "5") (pinfunction "GATE_5") (pintype "bidirectional"))
    )
    (net (code "55") (name "Net-(Q9-S)") (class "Default")
      (node (ref "M3+") (pin "P$1") (pinfunction "P$1_P$1") (pintype "bidirectional"))
      (node (ref "Q9") (pin "2") (pinfunction "S_2") (pintype "bidirectional"))
      (node (ref "R18") (pin "1") (pinfunction "1_1") (pintype "passive"))
    )
    (net (code "56") (name "Net-(Q11-D)") (class "Default")
      (node (ref "C28") (pin "2") (pinfunction "2_2") (pintype "passive"))
      (node (ref "Q11") (pin "TAB") (pinfunction "D_TAB") (pintype "bidirectional"))
      (node (ref "U$18") (pin "4") (pinfunction "IP-_4") (pintype "bidirectional"))
      (node (ref "U$9") (pin "6") (pinfunction "SENSE_6") (pintype "bidirectional"))
      (node (ref "U$9") (pin "8") (pinfunction "V+_8") (pintype "bidirectional"))
    )
    (net (code "57") (name "Net-(Q11-G)") (class "Default")
      (node (ref "Q11") (pin "1") (pinfunction "G_1") (pintype "bidirectional"))
      (node (ref "U$9") (pin "5") (pinfunction "GATE_5") (pintype "bidirectional"))
    )
    (net (code "58") (name "Net-(Q11-S)") (class "Default")
      (node (ref "M4+") (pin "P$1") (pinfunction "P$1_P$1") (pintype "bidirectional"))
      (node (ref "Q11") (pin "2") (pinfunction "S_2") (pintype "bidirectional"))
      (node (ref "R20") (pin "1") (pinfunction "1_1") (pintype "passive"))
    )
    (net (code "59") (name "Net-(Q12-G)") (class "Default")
      (node (ref "Q12") (pin "1") (pinfunction "G_1") (pintype "passive"))
      (node (ref "R15") (pin "1") (pinfunction "1_1") (pintype "passive"))
    )
    (net (code "60") (name "Net-(Q14-D)") (class "Default")
      (node (ref "C30") (pin "2") (pinfunction "2_2") (pintype "passive"))
      (node (ref "Q14") (pin "TAB") (pinfunction "D_TAB") (pintype "bidirectional"))
      (node (ref "U$10") (pin "6") (pinfunction "SENSE_6") (pintype "bidirectional"))
      (node (ref "U$10") (pin "8") (pinfunction "V+_8") (pintype "bidirectional"))
      (node (ref "U$17") (pin "4") (pinfunction "IP-_4") (pintype "bidirectional"))
    )
    (net (code "61") (name "Net-(Q14-G)") (class "Default")
      (node (ref "Q14") (pin "1") (pinfunction "G_1") (pintype "bidirectional"))
      (node (ref "U$10") (pin "5") (pinfunction "GATE_5") (pintype "bidirectional"))
    )
    (net (code "62") (name "Net-(Q14-S)") (class "Default")
      (node (ref "M5+") (pin "P$1") (pinfunction "P$1_P$1") (pintype "bidirectional"))
      (node (ref "Q14") (pin "2") (pinfunction "S_2") (pintype "bidirectional"))
      (node (ref "R22") (pin "1") (pinfunction "1_1") (pintype "passive"))
    )
    (net (code "63") (name "Net-(Q16-D)") (class "Default")
      (node (ref "C32") (pin "2") (pinfunction "2_2") (pintype "passive"))
      (node (ref "Q16") (pin "TAB") (pinfunction "D_TAB") (pintype "bidirectional"))
      (node (ref "U$11") (pin "6") (pinfunction "SENSE_6") (pintype "bidirectional"))
      (node (ref "U$11") (pin "8") (pinfunction "V+_8") (pintype "bidirectional"))
      (node (ref "U$16") (pin "4") (pinfunction "IP-_4") (pintype "bidirectional"))
    )
    (net (code "64") (name "Net-(Q16-G)") (class "Default")
      (node (ref "Q16") (pin "1") (pinfunction "G_1") (pintype "bidirectional"))
      (node (ref "U$11") (pin "5") (pinfunction "GATE_5") (pintype "bidirectional"))
    )
    (net (code "65") (name "Net-(Q16-S)") (class "Default")
      (node (ref "M6+") (pin "P$1") (pinfunction "P$1_P$1") (pintype "bidirectional"))
      (node (ref "Q16") (pin "2") (pinfunction "S_2") (pintype "bidirectional"))
      (node (ref "R24") (pin "1") (pinfunction "1_1") (pintype "passive"))
    )
    (net (code "66") (name "Net-(Q20-D)") (class "Default")
      (node (ref "C36") (pin "2") (pinfunction "2_2") (pintype "passive"))
      (node (ref "Q20") (pin "TAB") (pinfunction "D_TAB") (pintype "bidirectional"))
      (node (ref "U$13") (pin "6") (pinfunction "SENSE_6") (pintype "bidirectional"))
      (node (ref "U$13") (pin "8") (pinfunction "V+_8") (pintype "bidirectional"))
      (node (ref "U$20") (pin "4") (pinfunction "IP-_4") (pintype "bidirectional"))
    )
    (net (code "67") (name "Net-(Q20-G)") (class "Default")
      (node (ref "Q20") (pin "1") (pinfunction "G_1") (pintype "bidirectional"))
      (node (ref "U$13") (pin "5") (pinfunction "GATE_5") (pintype "bidirectional"))
    )
    (net (code "68") (name "Net-(Q20-S)") (class "Default")
      (node (ref "AUX1+") (pin "P$1") (pinfunction "P$1_P$1") (pintype "bidirectional"))
      (node (ref "Q20") (pin "2") (pinfunction "S_2") (pintype "bidirectional"))
      (node (ref "R28") (pin "1") (pinfunction "1_1") (pintype "passive"))
    )
    (net (code "69") (name "Net-(R1-Pad1)") (class "Default")
      (node (ref "R1") (pin "1") (pinfunction "1_1") (pintype "passive"))
      (node (ref "U$12") (pin "A") (pinfunction "A_A") (pintype "bidirectional"))
      (node (ref "U$5") (pin "1") (pinfunction "1_1") (pintype "bidirectional"))
    )
    (net (code "70") (name "Net-(R1-Pad2)") (class "Default")
      (node (ref "R1") (pin "2") (pinfunction "2_2") (pintype "passive"))
      (node (ref "U$12") (pin "B") (pinfunction "B_B") (pintype "bidirectional"))
      (node (ref "U$5") (pin "2") (pinfunction "2_2") (pintype "bidirectional"))
    )
    (net (code "71") (name "Net-(R2-Pad1)") (class "Default")
      (node (ref "R2") (pin "1") (pinfunction "1_1") (pintype "passive"))
      (node (ref "U$23") (pin "1") (pinfunction "1_1") (pintype "bidirectional"))
      (node (ref "U$24") (pin "A") (pinfunction "A_A") (pintype "bidirectional"))
    )
    (net (code "72") (name "Net-(R2-Pad2)") (class "Default")
      (node (ref "R2") (pin "2") (pinfunction "2_2") (pintype "passive"))
      (node (ref "U$23") (pin "2") (pinfunction "2_2") (pintype "bidirectional"))
      (node (ref "U$24") (pin "B") (pinfunction "B_B") (pintype "bidirectional"))
    )
    (net (code "73") (name "Net-(R6-Pad1)") (class "Default")
      (node (ref "R6") (pin "1") (pinfunction "1_1") (pintype "passive"))
      (node (ref "U$12") (pin "Z") (pinfunction "Z_Z") (pintype "bidirectional"))
      (node (ref "U$5") (pin "6") (pinfunction "6_6") (pintype "bidirectional"))
    )
    (net (code "74") (name "Net-(R6-Pad2)") (class "Default")
      (node (ref "R6") (pin "2") (pinfunction "2_2") (pintype "passive"))
      (node (ref "U$12") (pin "Y") (pinfunction "Y_Y") (pintype "bidirectional"))
      (node (ref "U$5") (pin "3") (pinfunction "3_3") (pintype "bidirectional"))
    )
    (net (code "75") (name "Net-(R7-Pad1)") (class "Default")
      (node (ref "R7") (pin "1") (pinfunction "1_1") (pintype "passive"))
      (node (ref "U$23") (pin "6") (pinfunction "6_6") (pintype "bidirectional"))
      (node (ref "U$24") (pin "Z") (pinfunction "Z_Z") (pintype "bidirectional"))
    )
    (net (code "76") (name "Net-(R7-Pad2)") (class "Default")
      (node (ref "R7") (pin "2") (pinfunction "2_2") (pintype "passive"))
      (node (ref "U$23") (pin "3") (pinfunction "3_3") (pintype "bidirectional"))
      (node (ref "U$24") (pin "Y") (pinfunction "Y_Y") (pintype "bidirectional"))
    )
    (net (code "77") (name "Net-(REY-5V-+SENSE)") (class "Default")
      (node (ref "C22") (pin "+") (pinfunction "+_+") (pintype "passive"))
      (node (ref "REY-5V") (pin "P$6") (pinfunction "+VOUT_P$6") (pintype "bidirectional"))
      (node (ref "REY-5V") (pin "P$7") (pinfunction "+SENSE_P$7") (pintype "bidirectional"))
      (node (ref "U$3") (pin "1") (pinfunction "IP+_1") (pintype "bidirectional"))
    )
    (net (code "78") (name "Net-(U$2-FILTER)") (class "Default")
      (node (ref "C9") (pin "1") (pinfunction "1_1") (pintype "passive"))
      (node (ref "U$2") (pin "6") (pinfunction "FILTER_6") (pintype "bidirectional"))
    )
    (net (code "79") (name "Net-(U$3-FILTER)") (class "Default")
      (node (ref "C12") (pin "1") (pinfunction "1_1") (pintype "passive"))
      (node (ref "U$3") (pin "6") (pinfunction "FILTER_6") (pintype "bidirectional"))
    )
    (net (code "80") (name "Net-(U$4-+3V3-Pad+3V3_1)") (class "Default")
      (node (ref "U$4") (pin "+3V3_1") (pinfunction "+3V3_+3V3_1") (pintype "bidirectional"))
      (node (ref "U$4") (pin "+3V3_2") (pinfunction "+3V3_+3V3_2") (pintype "bidirectional"))
    )
    (net (code "81") (name "Net-(U$4-RST-PadRST1)") (class "Default")
      (node (ref "U$4") (pin "RST1") (pinfunction "RST_RST1") (pintype "bidirectional"))
      (node (ref "U$4") (pin "RST_2") (pinfunction "RST_RST_2") (pintype "bidirectional"))
    )
    (net (code "82") (name "Net-(U$14-FILTER)") (class "Default")
      (node (ref "C37") (pin "1") (pinfunction "1_1") (pintype "passive"))
      (node (ref "U$14") (pin "6") (pinfunction "FILTER_6") (pintype "bidirectional"))
    )
    (net (code "83") (name "Net-(U$15-FILTER)") (class "Default")
      (node (ref "C38") (pin "1") (pinfunction "1_1") (pintype "passive"))
      (node (ref "U$15") (pin "6") (pinfunction "FILTER_6") (pintype "bidirectional"))
    )
    (net (code "84") (name "Net-(U$16-FILTER)") (class "Default")
      (node (ref "C27") (pin "1") (pinfunction "1_1") (pintype "passive"))
      (node (ref "U$16") (pin "6") (pinfunction "FILTER_6") (pintype "bidirectional"))
    )
    (net (code "85") (name "Net-(U$17-FILTER)") (class "Default")
      (node (ref "C31") (pin "1") (pinfunction "1_1") (pintype "passive"))
      (node (ref "U$17") (pin "6") (pinfunction "FILTER_6") (pintype "bidirectional"))
    )
    (net (code "86") (name "Net-(U$18-FILTER)") (class "Default")
      (node (ref "C35") (pin "1") (pinfunction "1_1") (pintype "passive"))
      (node (ref "U$18") (pin "6") (pinfunction "FILTER_6") (pintype "bidirectional"))
    )
    (net (code "87") (name "Net-(U$19-FILTER)") (class "Default")
      (node (ref "C40") (pin "1") (pinfunction "1_1") (pintype "passive"))
      (node (ref "U$19") (pin "6") (pinfunction "FILTER_6") (pintype "bidirectional"))
    )
    (net (code "88") (name "Net-(U$20-FILTER)") (class "Default")
      (node (ref "C42") (pin "1") (pinfunction "1_1") (pintype "passive"))
      (node (ref "U$20") (pin "6") (pinfunction "FILTER_6") (pintype "bidirectional"))
    )
    (net (code "89") (name "Net-(U$21-FILTER)") (class "Default")
      (node (ref "C43") (pin "1") (pinfunction "1_1") (pintype "passive"))
      (node (ref "U$21") (pin "6") (pinfunction "FILTER_6") (pintype "bidirectional"))
    )
    (net (code "90") (name "Net-(X1A-S)") (class "Default")
      (node (ref "M2-2") (pin "P$1") (pinfunction "P$1_P$1") (pintype "bidirectional"))
      (node (ref "X1") (pin "1") (pinfunction "S_1") (pintype "passive"))
    )
    (net (code "91") (name "Net-(X1B-S)") (class "Default")
      (node (ref "M2-4") (pin "P$1") (pinfunction "P$1_P$1") (pintype "bidirectional"))
      (node (ref "X1") (pin "2") (pinfunction "S_2") (pintype "passive"))
    )
    (net (code "92") (name "Net-(X1C-S)") (class "Default")
      (node (ref "M2-1") (pin "P$1") (pinfunction "P$1_P$1") (pintype "bidirectional"))
      (node (ref "X1") (pin "3") (pinfunction "S_3") (pintype "passive"))
    )
    (net (code "93") (name "Net-(X1D-S)") (class "Default")
      (node (ref "M2-3") (pin "P$1") (pinfunction "P$1_P$1") (pintype "bidirectional"))
      (node (ref "X1") (pin "4") (pinfunction "S_4") (pintype "passive"))
    )
    (net (code "94") (name "PRIMARY-VMEAS") (class "Default")
      (node (ref "R3") (pin "1") (pinfunction "1_1") (pintype "passive"))
      (node (ref "R4") (pin "2") (pinfunction "2_2") (pintype "passive"))
      (node (ref "U$4") (pin "PD7") (pinfunction "PD7_PD7") (pintype "bidirectional"))
    )
    (net (code "95") (name "V_BATT") (class "Default")
      (node (ref "BATT-POS") (pin "P$1") (pinfunction "P$1_P$1") (pintype "bidirectional"))
      (node (ref "BB-8-5V") (pin "1") (pinfunction "VI_1") (pintype "bidirectional"))
      (node (ref "C1") (pin "+") (pinfunction "+_+") (pintype "passive"))
      (node (ref "C2") (pin "+") (pinfunction "+_+") (pintype "passive"))
      (node (ref "C3") (pin "+") (pinfunction "+_+") (pintype "passive"))
      (node (ref "C4") (pin "+") (pinfunction "+_+") (pintype "passive"))
      (node (ref "D1") (pin "C") (pinfunction "C_C") (pintype "passive"))
      (node (ref "D2") (pin "C") (pinfunction "C_C") (pintype "passive"))
      (node (ref "FINN-12V") (pin "1") (pinfunction "+VIN_1") (pintype "bidirectional"))
      (node (ref "POE-12V") (pin "1") (pinfunction "+VIN_1") (pintype "bidirectional"))
      (node (ref "R3") (pin "2") (pinfunction "2_2") (pintype "passive"))
      (node (ref "REY-5V") (pin "P$3") (pinfunction "+VIN_P$3") (pintype "bidirectional"))
      (node (ref "U$14") (pin "1") (pinfunction "IP+_1") (pintype "bidirectional"))
      (node (ref "U$15") (pin "1") (pinfunction "IP+_1") (pintype "bidirectional"))
      (node (ref "U$16") (pin "1") (pinfunction "IP+_1") (pintype "bidirectional"))
      (node (ref "U$17") (pin "1") (pinfunction "IP+_1") (pintype "bidirectional"))
      (node (ref "U$18") (pin "1") (pinfunction "IP+_1") (pintype "bidirectional"))
      (node (ref "U$19") (pin "1") (pinfunction "IP+_1") (pintype "bidirectional"))
      (node (ref "U$2") (pin "1") (pinfunction "IP+_1") (pintype "bidirectional"))
      (node (ref "U$20") (pin "1") (pinfunction "IP+_1") (pintype "bidirectional"))
    )
    (net (code "96") (name "unconnected-(REY-5V-TRIM-PadP$4)") (class "Default")
      (node (ref "REY-5V") (pin "P$4") (pinfunction "TRIM_P$4") (pintype "bidirectional"))
    )
    (net (code "97") (name "unconnected-(U$1-FAULT-Pad3)") (class "Default")
      (node (ref "U$1") (pin "3") (pinfunction "FAULT_3") (pintype "bidirectional"))
    )
    (net (code "98") (name "unconnected-(U$1-TIMER-Pad2)") (class "Default")
      (node (ref "U$1") (pin "2") (pinfunction "TIMER_2") (pintype "bidirectional"))
    )
    (net (code "99") (name "unconnected-(U$4-PadPA4)") (class "Default")
      (node (ref "U$4") (pin "PA4") (pinfunction "PA4_PA4") (pintype "bidirectional"))
    )
    (net (code "100") (name "unconnected-(U$4-PadPA5)") (class "Default")
      (node (ref "U$4") (pin "PA5") (pinfunction "PA5_PA5") (pintype "bidirectional"))
    )
    (net (code "101") (name "unconnected-(U$4-PadPA6)") (class "Default")
      (node (ref "U$4") (pin "PA6") (pinfunction "PA6_PA6") (pintype "bidirectional"))
    )
    (net (code "102") (name "unconnected-(U$4-PadPB2)") (class "Default")
      (node (ref "U$4") (pin "PB2") (pinfunction "PB2_PB2") (pintype "bidirectional"))
    )
    (net (code "103") (name "unconnected-(U$4-PadPB3)") (class "Default")
      (node (ref "U$4") (pin "PB3") (pinfunction "PB3_PB3") (pintype "bidirectional"))
    )
    (net (code "104") (name "unconnected-(U$4-PadPC6)") (class "Default")
      (node (ref "U$4") (pin "PC6") (pinfunction "PC6_PC6") (pintype "bidirectional"))
    )
    (net (code "105") (name "unconnected-(U$4-PadPC7)") (class "Default")
      (node (ref "U$4") (pin "PC7") (pinfunction "PC7_PC7") (pintype "bidirectional"))
    )
    (net (code "106") (name "unconnected-(U$4-PadPD3)") (class "Default")
      (node (ref "U$4") (pin "PD3") (pinfunction "PD3_PD3") (pintype "bidirectional"))
    )
    (net (code "107") (name "unconnected-(U$4-PadPD5)") (class "Default")
      (node (ref "U$4") (pin "PD5") (pinfunction "PD5_PD5") (pintype "bidirectional"))
    )
    (net (code "108") (name "unconnected-(U$4-PadPE0)") (class "Default")
      (node (ref "U$4") (pin "PE0") (pinfunction "PE0_PE0") (pintype "bidirectional"))
    )
    (net (code "109") (name "unconnected-(U$4-PadPE1)") (class "Default")
      (node (ref "U$4") (pin "PE1") (pinfunction "PE1_PE1") (pintype "bidirectional"))
    )
    (net (code "110") (name "unconnected-(U$4-PadPE2)") (class "Default")
      (node (ref "U$4") (pin "PE2") (pinfunction "PE2_PE2") (pintype "bidirectional"))
    )
    (net (code "111") (name "unconnected-(U$4-PadPE3)") (class "Default")
      (node (ref "U$4") (pin "PE3") (pinfunction "PE3_PE3") (pintype "bidirectional"))
    )
    (net (code "112") (name "unconnected-(U$4-PadPE4)") (class "Default")
      (node (ref "U$4") (pin "PE4") (pinfunction "PE4_PE4") (pintype "bidirectional"))
    )
    (net (code "113") (name "unconnected-(U$4-PadPE5)") (class "Default")
      (node (ref "U$4") (pin "PE5") (pinfunction "PE5_PE5") (pintype "bidirectional"))
    )
    (net (code "114") (name "unconnected-(U$4-PadPF1)") (class "Default")
      (node (ref "U$4") (pin "PF1") (pinfunction "PF1_PF1") (pintype "bidirectional"))
    )
    (net (code "115") (name "unconnected-(U$4-PadPF2)") (class "Default")
      (node (ref "U$4") (pin "PF2") (pinfunction "PF2_PF2") (pintype "bidirectional"))
    )
    (net (code "116") (name "unconnected-(U$4-PadPF3)") (class "Default")
      (node (ref "U$4") (pin "PF3") (pinfunction "PF3_PF3") (pintype "bidirectional"))
    )
    (net (code "117") (name "unconnected-(U$4-PadPG0)") (class "Default")
      (node (ref "U$4") (pin "PG0") (pinfunction "PG0_PG0") (pintype "bidirectional"))
    )
    (net (code "118") (name "unconnected-(U$4-PadPG1)") (class "Default")
      (node (ref "U$4") (pin "PG1") (pinfunction "PG1_PG1") (pintype "bidirectional"))
    )
    (net (code "119") (name "unconnected-(U$4-PadPH2)") (class "Default")
      (node (ref "U$4") (pin "PH2") (pinfunction "PH2_PH2") (pintype "bidirectional"))
    )
    (net (code "120") (name "unconnected-(U$4-PadPH3)") (class "Default")
      (node (ref "U$4") (pin "PH3") (pinfunction "PH3_PH3") (pintype "bidirectional"))
    )
    (net (code "121") (name "unconnected-(U$4-PadPK4)") (class "Default")
      (node (ref "U$4") (pin "PK4") (pinfunction "PK4_PK4") (pintype "bidirectional"))
    )
    (net (code "122") (name "unconnected-(U$4-PadPK5)") (class "Default")
      (node (ref "U$4") (pin "PK5") (pinfunction "PK5_PK5") (pintype "bidirectional"))
    )
    (net (code "123") (name "unconnected-(U$4-PadPL0)") (class "Default")
      (node (ref "U$4") (pin "PL0") (pinfunction "PL0_PL0") (pintype "bidirectional"))
    )
    (net (code "124") (name "unconnected-(U$4-PadPL1)") (class "Default")
      (node (ref "U$4") (pin "PL1") (pinfunction "PL1_PL1") (pintype "bidirectional"))
    )
    (net (code "125") (name "unconnected-(U$4-PadPL2)") (class "Default")
      (node (ref "U$4") (pin "PL2") (pinfunction "PL2_PL2") (pintype "bidirectional"))
    )
    (net (code "126") (name "unconnected-(U$4-PadPL3)") (class "Default")
      (node (ref "U$4") (pin "PL3") (pinfunction "PL3_PL3") (pintype "bidirectional"))
    )
    (net (code "127") (name "unconnected-(U$4-PadPL4)") (class "Default")
      (node (ref "U$4") (pin "PL4") (pinfunction "PL4_PL4") (pintype "bidirectional"))
    )
    (net (code "128") (name "unconnected-(U$4-PadPL5)") (class "Default")
      (node (ref "U$4") (pin "PL5") (pinfunction "PL5_PL5") (pintype "bidirectional"))
    )
    (net (code "129") (name "unconnected-(U$4-PadPM0)") (class "Default")
      (node (ref "U$4") (pin "PM0") (pinfunction "PM0_PM0") (pintype "bidirectional"))
    )
    (net (code "130") (name "unconnected-(U$4-PadPM1)") (class "Default")
      (node (ref "U$4") (pin "PM1") (pinfunction "PM1_PM1") (pintype "bidirectional"))
    )
    (net (code "131") (name "unconnected-(U$4-PadPM2)") (class "Default")
      (node (ref "U$4") (pin "PM2") (pinfunction "PM2_PM2") (pintype "bidirectional"))
    )
    (net (code "132") (name "unconnected-(U$4-PadPM3)") (class "Default")
      (node (ref "U$4") (pin "PM3") (pinfunction "PM3_PM3") (pintype "bidirectional"))
    )
    (net (code "133") (name "unconnected-(U$4-PadPM4)") (class "Default")
      (node (ref "U$4") (pin "PM4") (pinfunction "PM4_PM4") (pintype "bidirectional"))
    )
    (net (code "134") (name "unconnected-(U$4-PadPM5)") (class "Default")
      (node (ref "U$4") (pin "PM5") (pinfunction "PM5_PM5") (pintype "bidirectional"))
    )
    (net (code "135") (name "unconnected-(U$4-PadPM6)") (class "Default")
      (node (ref "U$4") (pin "PM6") (pinfunction "PM6_PM6") (pintype "bidirectional"))
    )
    (net (code "136") (name "unconnected-(U$4-PadPM7)") (class "Default")
      (node (ref "U$4") (pin "PM7") (pinfunction "PM7_PM7") (pintype "bidirectional"))
    )
    (net (code "137") (name "unconnected-(U$4-PadPN2)") (class "Default")
      (node (ref "U$4") (pin "PN2") (pinfunction "PN2_PN2") (pintype "bidirectional"))
    )
    (net (code "138") (name "unconnected-(U$4-PadPN4)") (class "Default")
      (node (ref "U$4") (pin "PN4") (pinfunction "PN4_PN4") (pintype "bidirectional"))
    )
    (net (code "139") (name "unconnected-(U$4-PadPN5)") (class "Default")
      (node (ref "U$4") (pin "PN5") (pinfunction "PN5_PN5") (pintype "bidirectional"))
    )
    (net (code "140") (name "unconnected-(U$4-PadPP4)") (class "Default")
      (node (ref "U$4") (pin "PP4") (pinfunction "PP4_PP4") (pintype "bidirectional"))
    )
    (net (code "141") (name "unconnected-(U$4-PadPQ0)") (class "Default")
      (node (ref "U$4") (pin "PQ0") (pinfunction "PQ0_PQ0") (pintype "bidirectional"))
    )
    (net (code "142") (name "unconnected-(U$4-PadPQ2{slash}PA3)") (class "Default")
      (node (ref "U$4") (pin "PQ2/PA3") (pinfunction "PQ2/PA3_PQ2/PA3") (pintype "bidirectional"))
    )
    (net (code "143") (name "unconnected-(U$4-PadPQ3{slash}PA2)") (class "Default")
      (node (ref "U$4") (pin "PQ3/PA2") (pinfunction "PQ3/PA2_PQ3/PA2") (pintype "bidirectional"))
    )
    (net (code "144") (name "unconnected-(U$5-Pad4)") (class "Default")
      (node (ref "U$5") (pin "4") (pinfunction "4_4") (pintype "bidirectional"))
    )
    (net (code "145") (name "unconnected-(U$5-Pad5)") (class "Default")
      (node (ref "U$5") (pin "5") (pinfunction "5_5") (pintype "bidirectional"))
    )
    (net (code "146") (name "unconnected-(U$6-FAULT-Pad3)") (class "Default")
      (node (ref "U$6") (pin "3") (pinfunction "FAULT_3") (pintype "bidirectional"))
    )
    (net (code "147") (name "unconnected-(U$6-TIMER-Pad2)") (class "Default")
      (node (ref "U$6") (pin "2") (pinfunction "TIMER_2") (pintype "bidirectional"))
    )
    (net (code "148") (name "unconnected-(U$7-FAULT-Pad3)") (class "Default")
      (node (ref "U$7") (pin "3") (pinfunction "FAULT_3") (pintype "bidirectional"))
    )
    (net (code "149") (name "unconnected-(U$7-TIMER-Pad2)") (class "Default")
      (node (ref "U$7") (pin "2") (pinfunction "TIMER_2") (pintype "bidirectional"))
    )
    (net (code "150") (name "unconnected-(U$8-FAULT-Pad3)") (class "Default")
      (node (ref "U$8") (pin "3") (pinfunction "FAULT_3") (pintype "bidirectional"))
    )
    (net (code "151") (name "unconnected-(U$8-TIMER-Pad2)") (class "Default")
      (node (ref "U$8") (pin "2") (pinfunction "TIMER_2") (pintype "bidirectional"))
    )
    (net (code "152") (name "unconnected-(U$9-FAULT-Pad3)") (class "Default")
      (node (ref "U$9") (pin "3") (pinfunction "FAULT_3") (pintype "bidirectional"))
    )
    (net (code "153") (name "unconnected-(U$9-TIMER-Pad2)") (class "Default")
      (node (ref "U$9") (pin "2") (pinfunction "TIMER_2") (pintype "bidirectional"))
    )
    (net (code "154") (name "unconnected-(U$10-FAULT-Pad3)") (class "Default")
      (node (ref "U$10") (pin "3") (pinfunction "FAULT_3") (pintype "bidirectional"))
    )
    (net (code "155") (name "unconnected-(U$10-TIMER-Pad2)") (class "Default")
      (node (ref "U$10") (pin "2") (pinfunction "TIMER_2") (pintype "bidirectional"))
    )
    (net (code "156") (name "unconnected-(U$11-FAULT-Pad3)") (class "Default")
      (node (ref "U$11") (pin "3") (pinfunction "FAULT_3") (pintype "bidirectional"))
    )
    (net (code "157") (name "unconnected-(U$11-TIMER-Pad2)") (class "Default")
      (node (ref "U$11") (pin "2") (pinfunction "TIMER_2") (pintype "bidirectional"))
    )
    (net (code "158") (name "unconnected-(U$13-FAULT-Pad3)") (class "Default")
      (node (ref "U$13") (pin "3") (pinfunction "FAULT_3") (pintype "bidirectional"))
    )
    (net (code "159") (name "unconnected-(U$13-TIMER-Pad2)") (class "Default")
      (node (ref "U$13") (pin "2") (pinfunction "TIMER_2") (pintype "bidirectional"))
    )
    (net (code "160") (name "unconnected-(U$23-Pad4)") (class "Default")
      (node (ref "U$23") (pin "4") (pinfunction "4_4") (pintype "bidirectional"))
    )
    (net (code "161") (name "unconnected-(U$23-Pad5)") (class "Default")
      (node (ref "U$23") (pin "5") (pinfunction "5_5") (pintype "bidirectional"))
    )
  )
)
